# slice_v7_zp.net
KiCad netlist of a schematic drawn in EAGLE
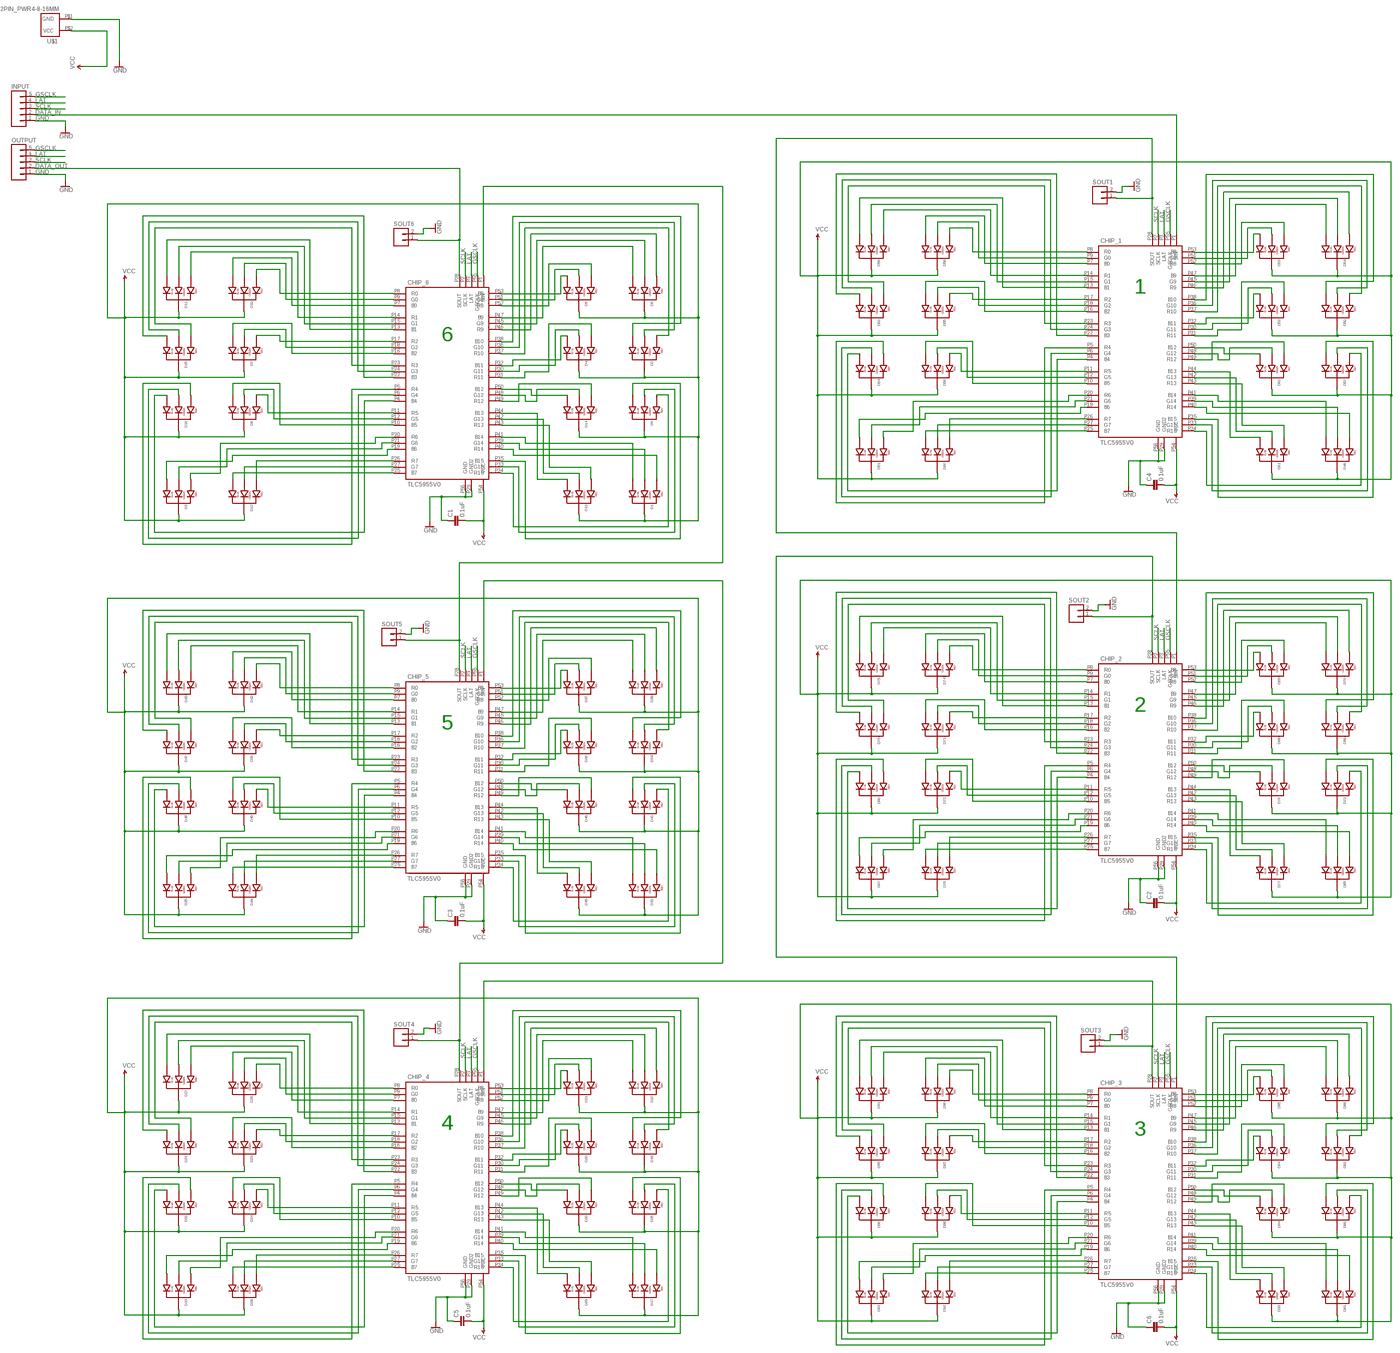
[diagram p0: schematic, sheet 1, overview]
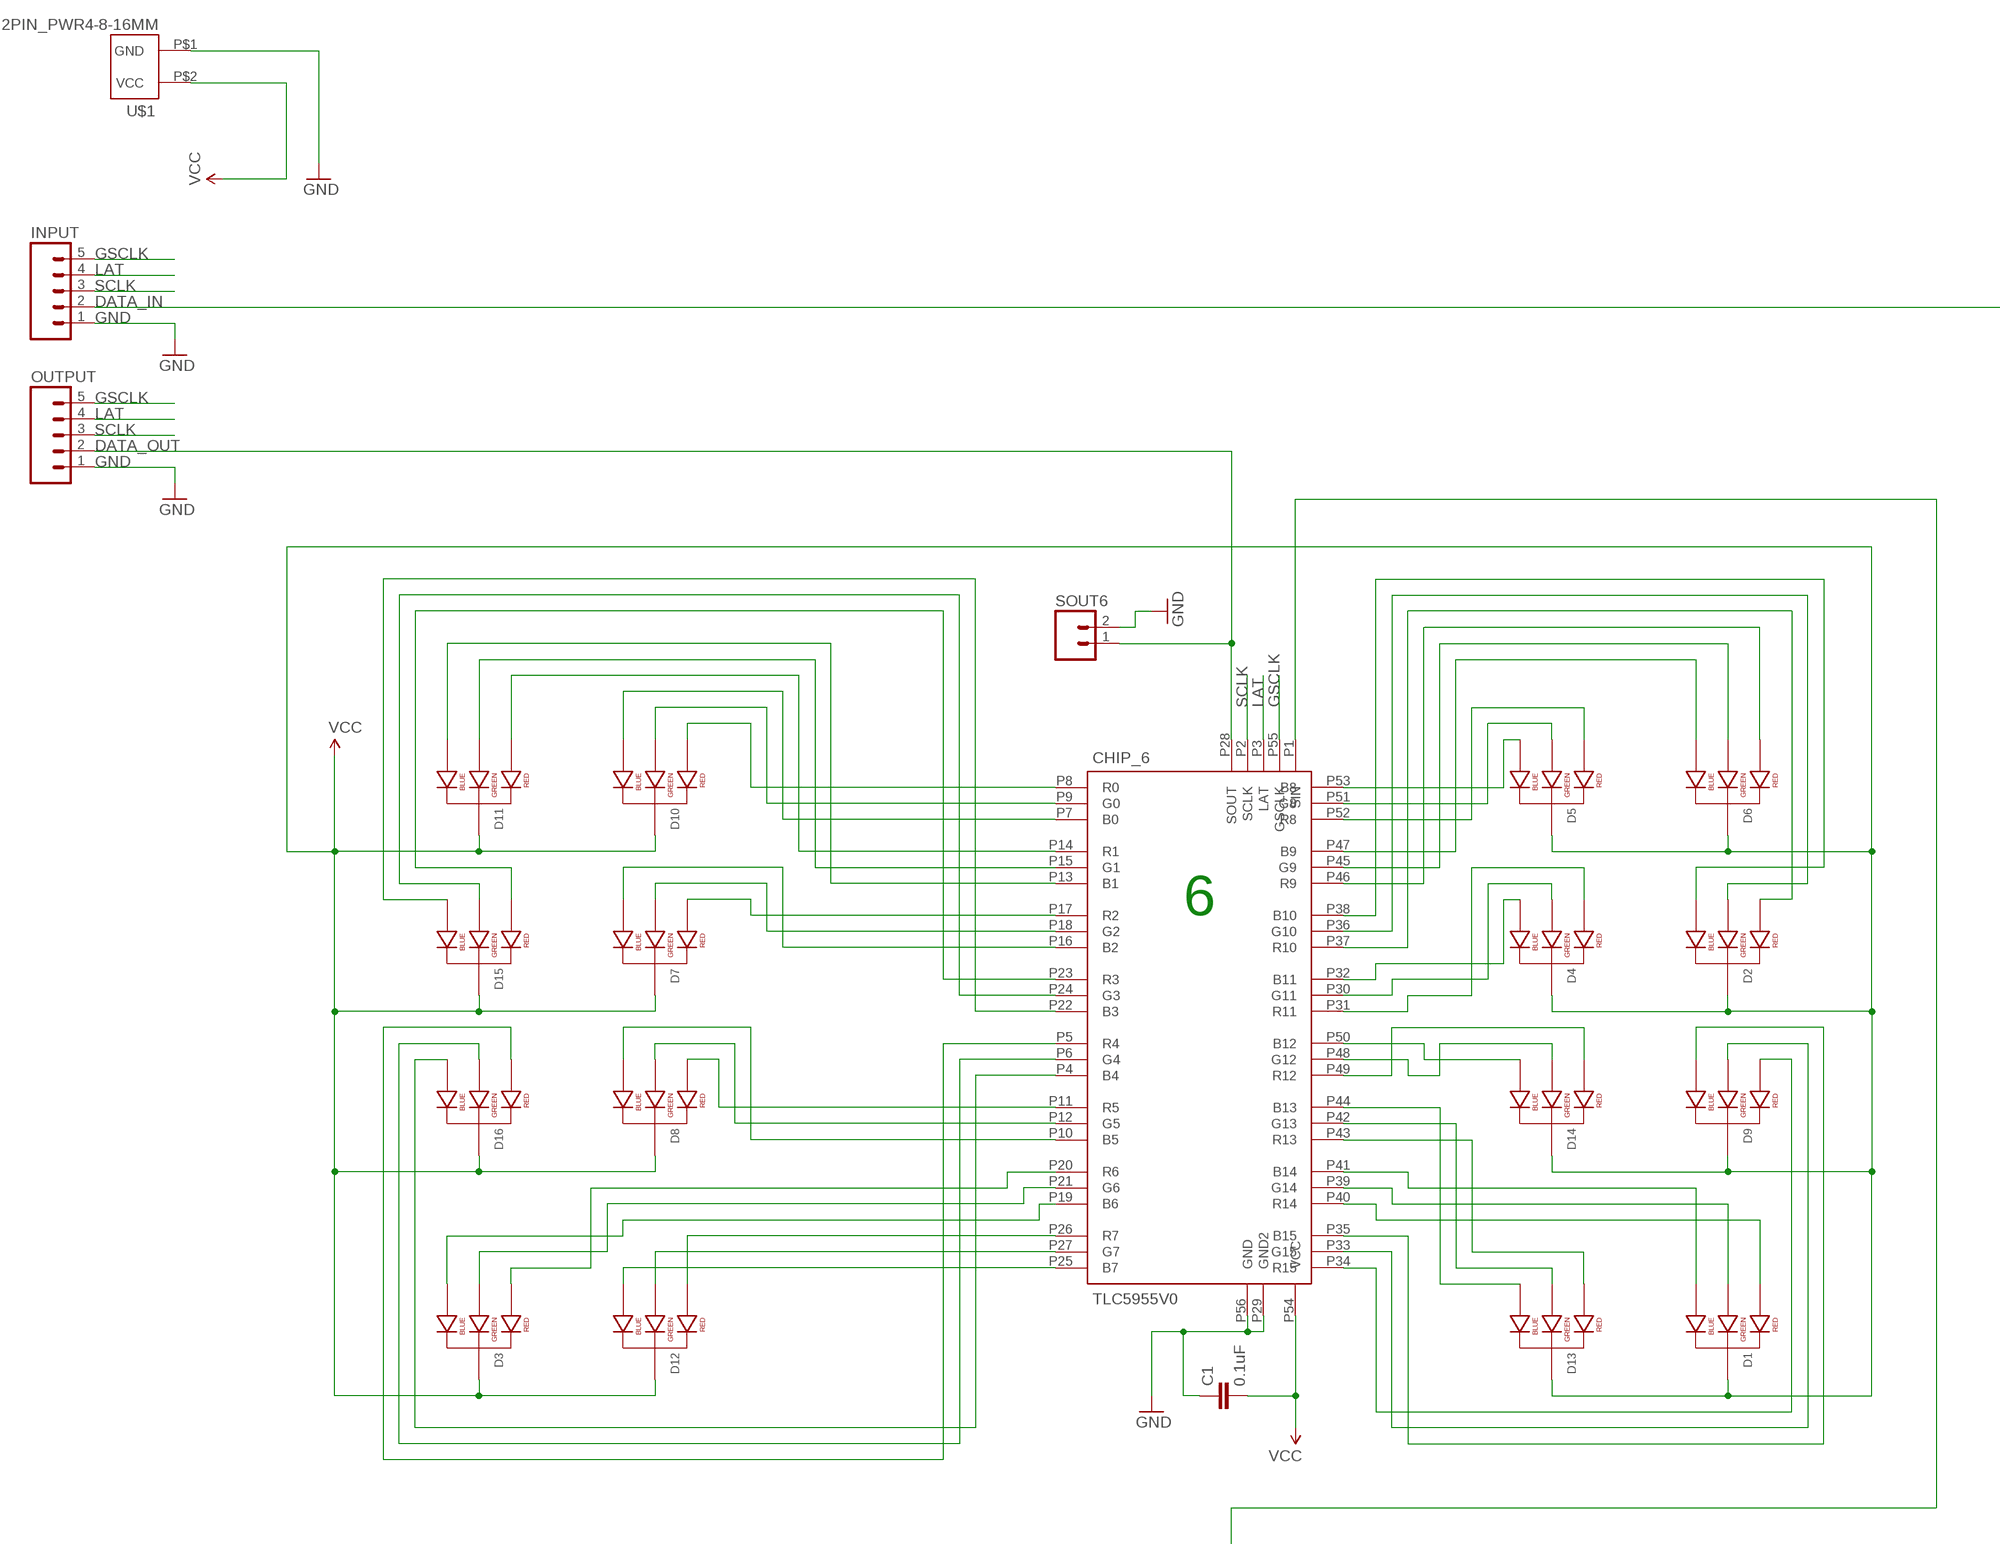
[diagram p1: schematic, sheet 1, part 1 of 4]
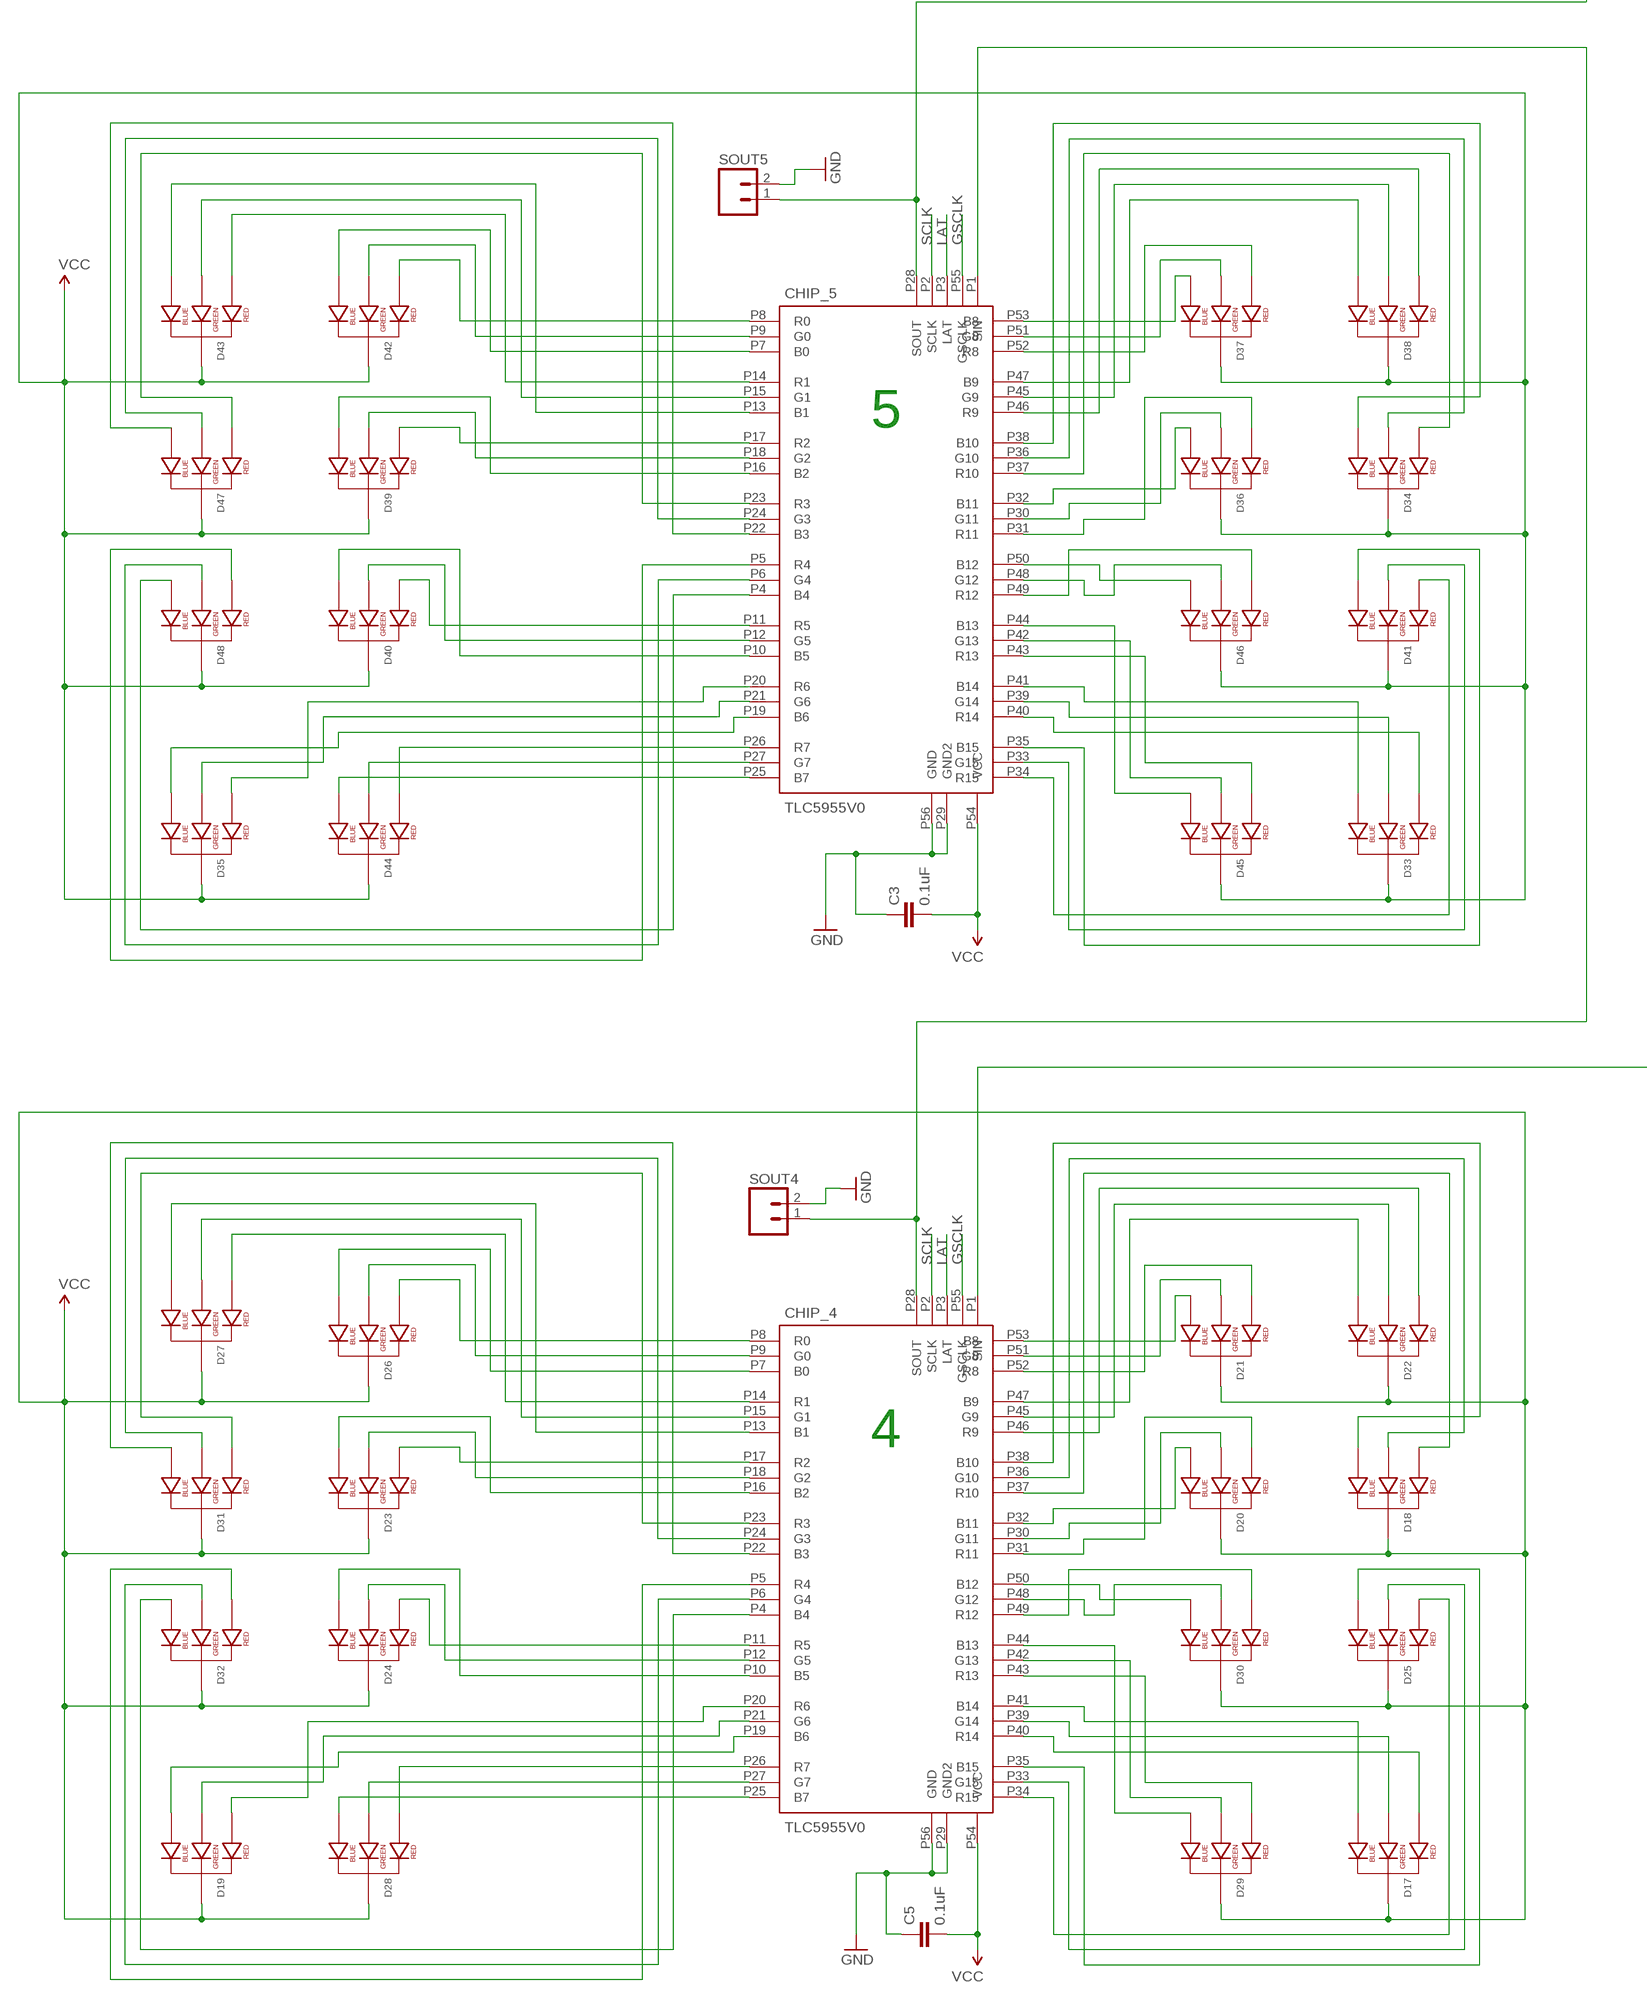
[diagram p2: schematic, sheet 1, part 2 of 4]
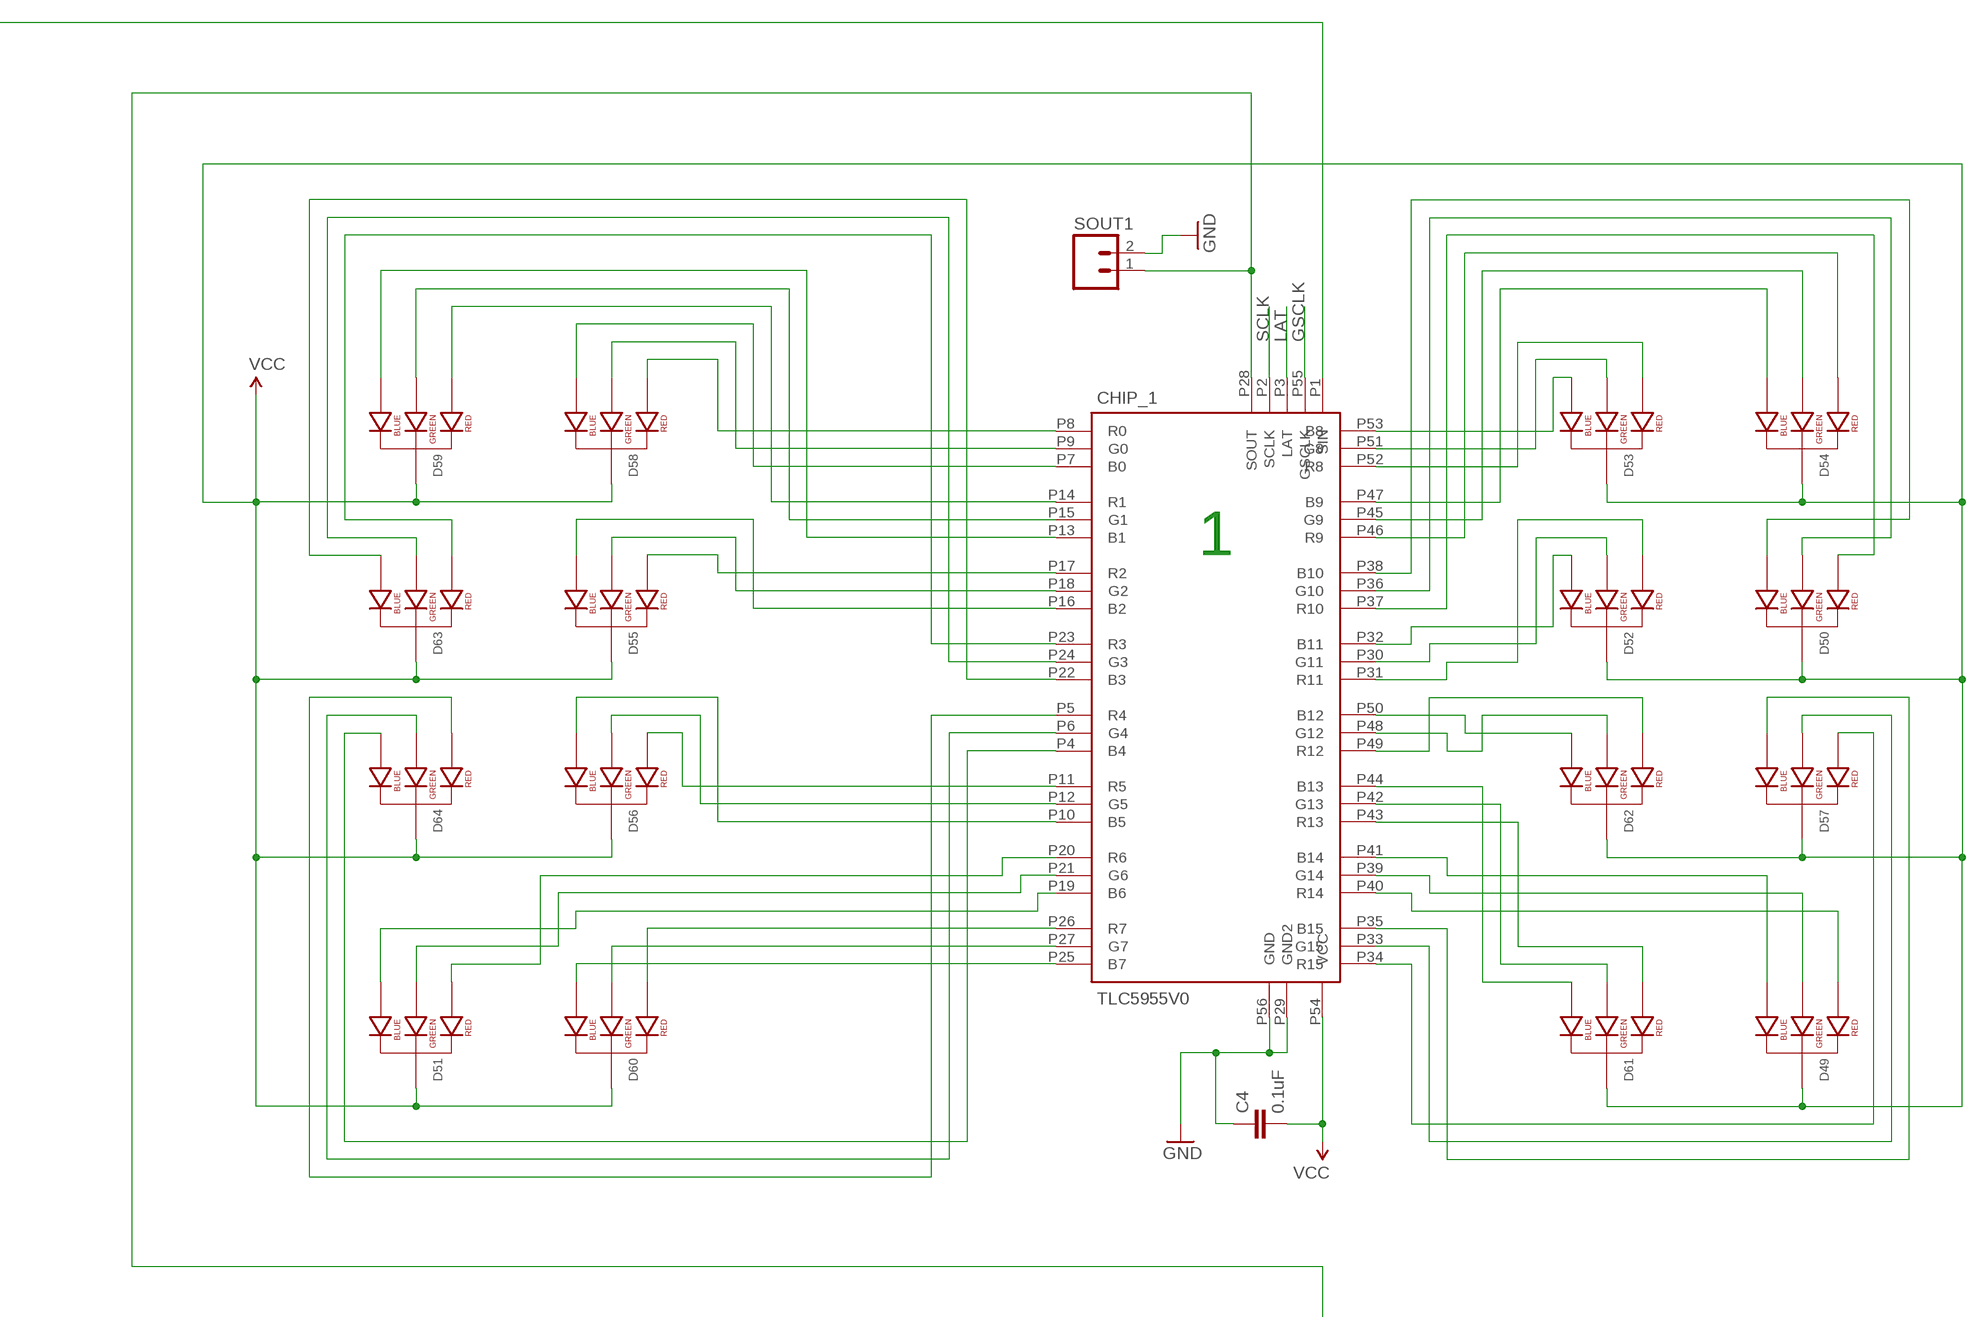
[diagram p3: schematic, sheet 1, part 3 of 4]
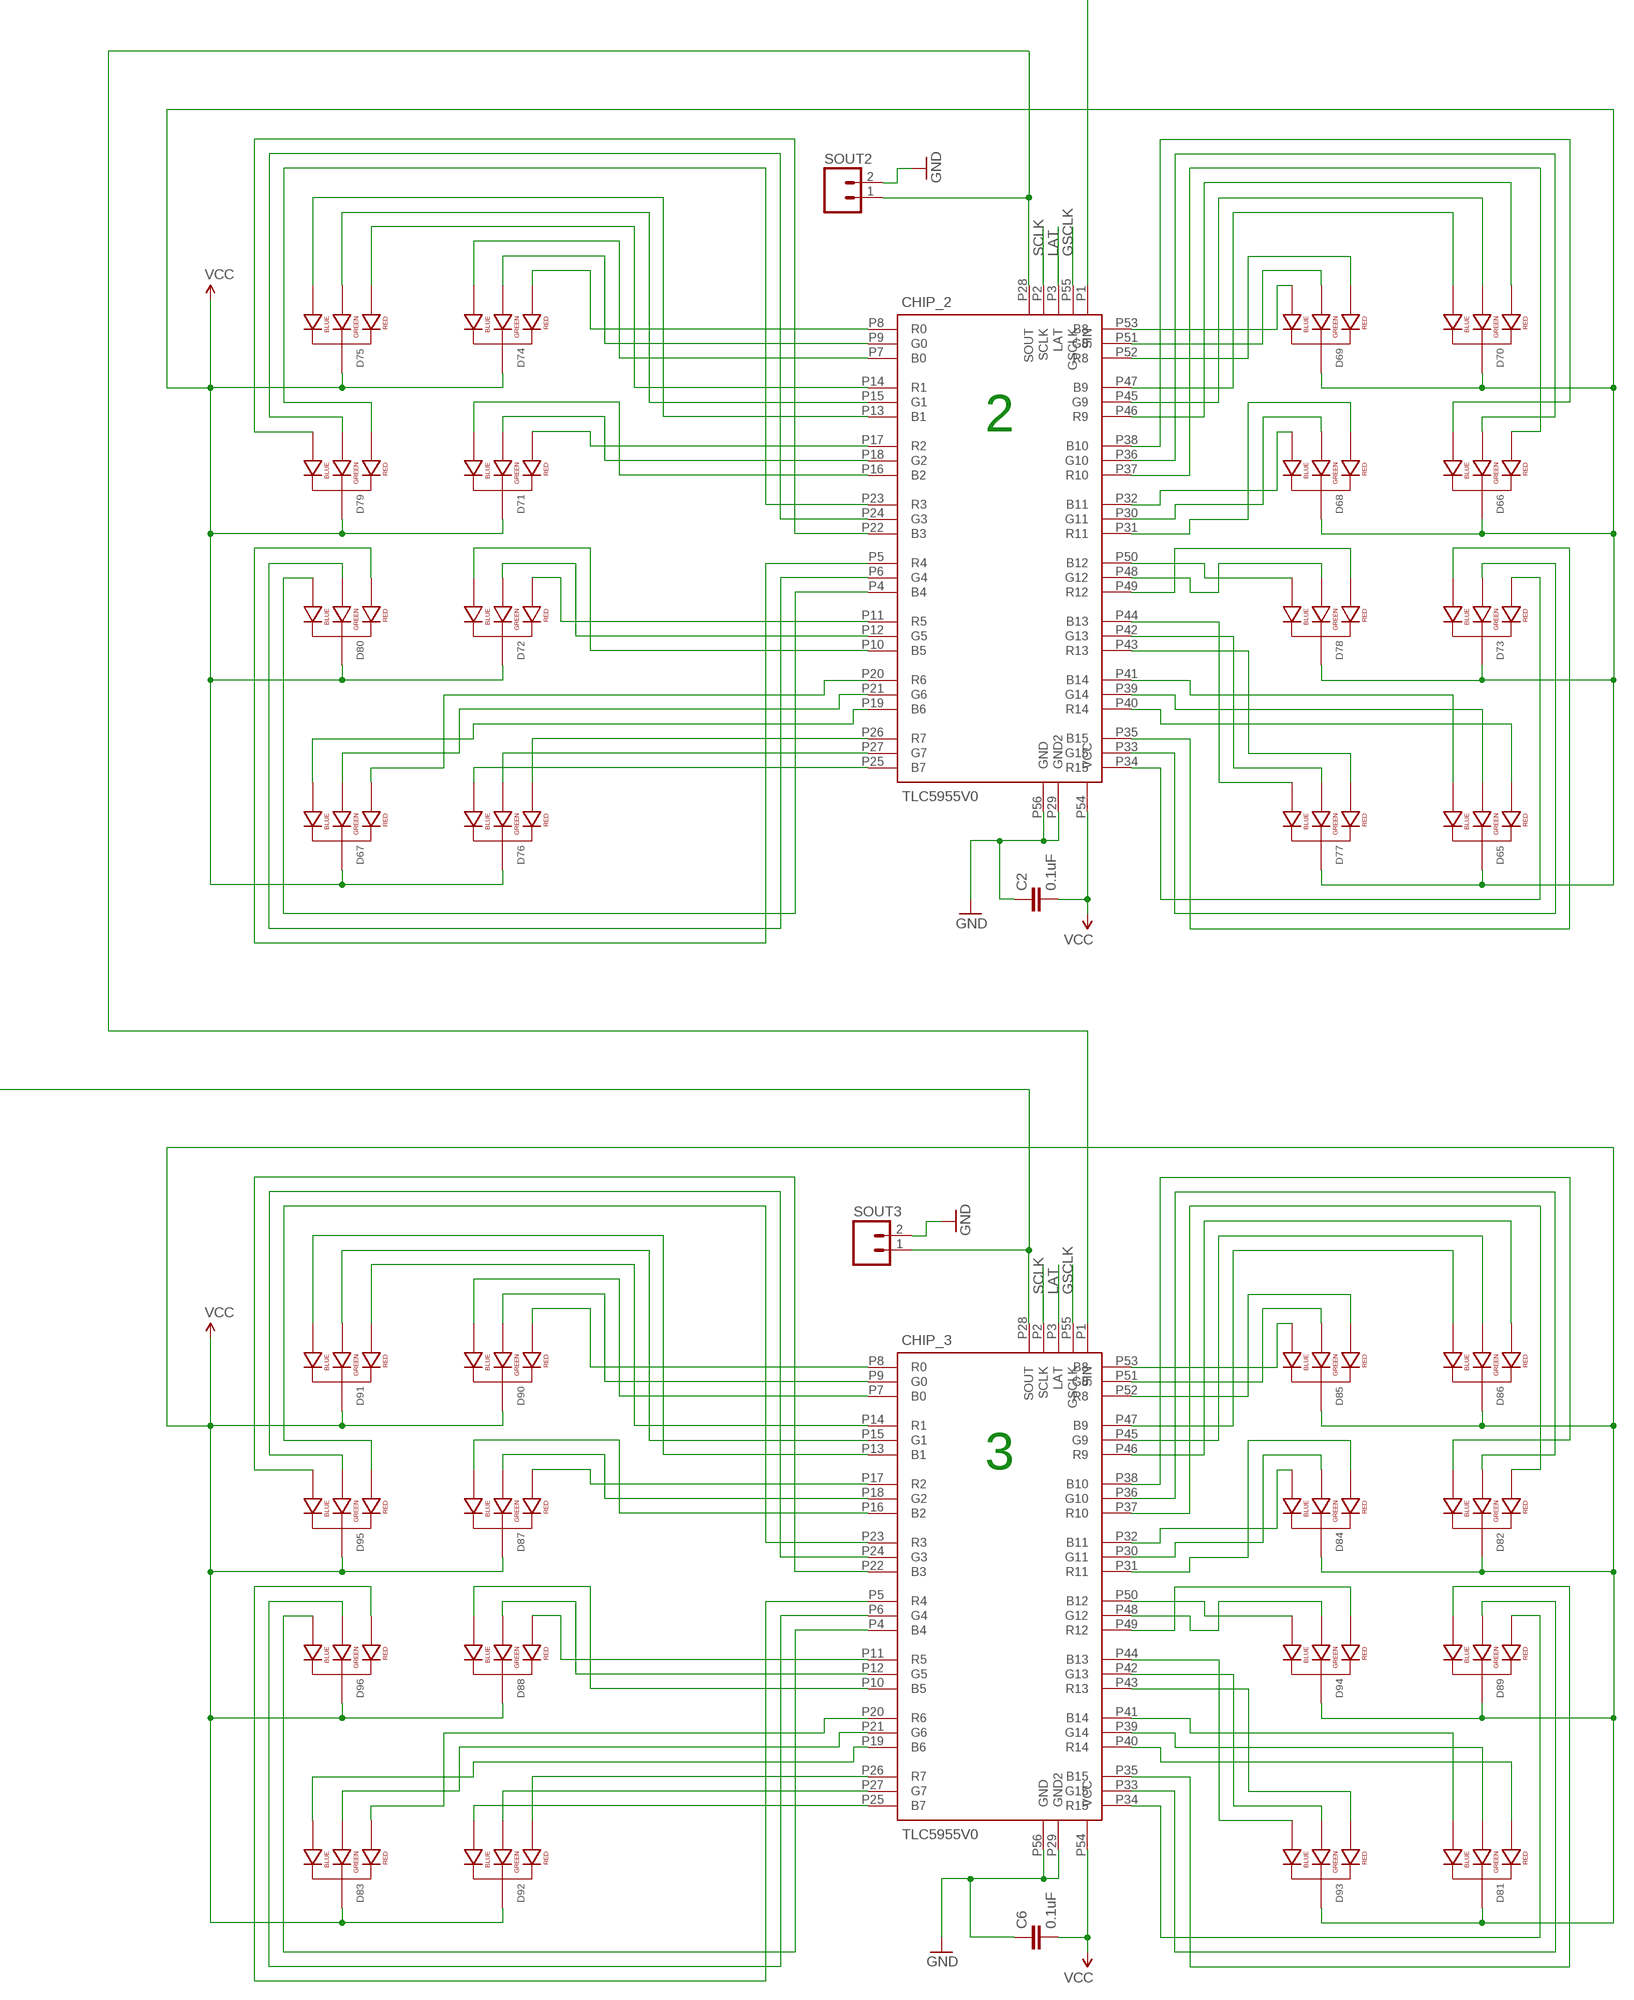
[diagram p4: schematic, sheet 1, part 4 of 4]

(export (version "E")
  (design (tool "Eeschema 10.0.6"))
  (components
    (comp (ref "C1")
      (value "0.1uF")
      (footprint "eagle-import:0603-CAP")
      (libsource (lib "eagle-import") (part "0.1UF-25V(+80/-20%)(0603)"))
    )
    (comp (ref "C2")
      (value "0.1uF")
      (footprint "eagle-import:0603-CAP")
      (libsource (lib "eagle-import") (part "0.1UF-25V(+80/-20%)(0603)"))
    )
    (comp (ref "C3")
      (value "0.1uF")
      (footprint "eagle-import:0603-CAP")
      (libsource (lib "eagle-import") (part "0.1UF-25V(+80/-20%)(0603)"))
    )
    (comp (ref "C4")
      (value "0.1uF")
      (footprint "eagle-import:0603-CAP")
      (libsource (lib "eagle-import") (part "0.1UF-25V(+80/-20%)(0603)"))
    )
    (comp (ref "C5")
      (value "0.1uF")
      (footprint "eagle-import:0603-CAP")
      (libsource (lib "eagle-import") (part "0.1UF-25V(+80/-20%)(0603)"))
    )
    (comp (ref "C6")
      (value "0.1uF")
      (footprint "eagle-import:0603-CAP")
      (libsource (lib "eagle-import") (part "0.1UF-25V(+80/-20%)(0603)"))
    )
    (comp (ref "CHIP_1")
      (value "TLC5955V0")
      (footprint "eagle-import:56-HTSSOP")
      (libsource (lib "eagle-import") (part "TLC5955V0"))
    )
    (comp (ref "CHIP_2")
      (value "TLC5955V0")
      (footprint "eagle-import:56-HTSSOP")
      (libsource (lib "eagle-import") (part "TLC5955V0"))
    )
    (comp (ref "CHIP_3")
      (value "TLC5955V0")
      (footprint "eagle-import:56-HTSSOP")
      (libsource (lib "eagle-import") (part "TLC5955V0"))
    )
    (comp (ref "CHIP_4")
      (value "TLC5955V0")
      (footprint "eagle-import:56-HTSSOP")
      (libsource (lib "eagle-import") (part "TLC5955V0"))
    )
    (comp (ref "CHIP_5")
      (value "TLC5955V0")
      (footprint "eagle-import:56-HTSSOP")
      (libsource (lib "eagle-import") (part "TLC5955V0"))
    )
    (comp (ref "CHIP_6")
      (value "TLC5955V0")
      (footprint "eagle-import:56-HTSSOP")
      (libsource (lib "eagle-import") (part "TLC5955V0"))
    )
    (comp (ref "D1")
      (value "LED-RGB-CC-THRUCLEAR")
      (footprint "eagle-import:LED-RGB-THRU")
      (libsource (lib "eagle-import") (part "LED-RGB-CC-THRUCLEAR"))
    )
    (comp (ref "D2")
      (value "LED-RGB-CC-THRUCLEAR")
      (footprint "eagle-import:LED-RGB-THRU")
      (libsource (lib "eagle-import") (part "LED-RGB-CC-THRUCLEAR"))
    )
    (comp (ref "D3")
      (value "LED-RGB-CC-THRUCLEAR")
      (footprint "eagle-import:LED-RGB-THRU")
      (libsource (lib "eagle-import") (part "LED-RGB-CC-THRUCLEAR"))
    )
    (comp (ref "D4")
      (value "LED-RGB-CC-THRUCLEAR")
      (footprint "eagle-import:LED-RGB-THRU")
      (libsource (lib "eagle-import") (part "LED-RGB-CC-THRUCLEAR"))
    )
    (comp (ref "D5")
      (value "LED-RGB-CC-THRUCLEAR")
      (footprint "eagle-import:LED-RGB-THRU")
      (libsource (lib "eagle-import") (part "LED-RGB-CC-THRUCLEAR"))
    )
    (comp (ref "D6")
      (value "LED-RGB-CC-THRUCLEAR")
      (footprint "eagle-import:LED-RGB-THRU")
      (libsource (lib "eagle-import") (part "LED-RGB-CC-THRUCLEAR"))
    )
    (comp (ref "D7")
      (value "LED-RGB-CC-THRUCLEAR")
      (footprint "eagle-import:LED-RGB-THRU")
      (libsource (lib "eagle-import") (part "LED-RGB-CC-THRUCLEAR"))
    )
    (comp (ref "D8")
      (value "LED-RGB-CC-THRUCLEAR")
      (footprint "eagle-import:LED-RGB-THRU")
      (libsource (lib "eagle-import") (part "LED-RGB-CC-THRUCLEAR"))
    )
    (comp (ref "D9")
      (value "LED-RGB-CC-THRUCLEAR")
      (footprint "eagle-import:LED-RGB-THRU")
      (libsource (lib "eagle-import") (part "LED-RGB-CC-THRUCLEAR"))
    )
    (comp (ref "D10")
      (value "LED-RGB-CC-THRUCLEAR")
      (footprint "eagle-import:LED-RGB-THRU")
      (libsource (lib "eagle-import") (part "LED-RGB-CC-THRUCLEAR"))
    )
    (comp (ref "D11")
      (value "LED-RGB-CC-THRUDIFFUSE")
      (footprint "eagle-import:LED-RGB-THRU")
      (libsource (lib "eagle-import") (part "LED-RGB-CC-THRUCLEAR"))
    )
    (comp (ref "D12")
      (value "LED-RGB-CC-THRUCLEAR")
      (footprint "eagle-import:LED-RGB-THRU")
      (libsource (lib "eagle-import") (part "LED-RGB-CC-THRUCLEAR"))
    )
    (comp (ref "D13")
      (value "LED-RGB-CC-THRUCLEAR")
      (footprint "eagle-import:LED-RGB-THRU")
      (libsource (lib "eagle-import") (part "LED-RGB-CC-THRUCLEAR"))
    )
    (comp (ref "D14")
      (value "LED-RGB-CC-THRUCLEAR")
      (footprint "eagle-import:LED-RGB-THRU")
      (libsource (lib "eagle-import") (part "LED-RGB-CC-THRUCLEAR"))
    )
    (comp (ref "D15")
      (value "LED-RGB-CC-THRUCLEAR")
      (footprint "eagle-import:LED-RGB-THRU")
      (libsource (lib "eagle-import") (part "LED-RGB-CC-THRUCLEAR"))
    )
    (comp (ref "D16")
      (value "LED-RGB-CC-THRUCLEAR")
      (footprint "eagle-import:LED-RGB-THRU")
      (libsource (lib "eagle-import") (part "LED-RGB-CC-THRUCLEAR"))
    )
    (comp (ref "D17")
      (value "LED-RGB-CC-THRUCLEAR")
      (footprint "eagle-import:LED-RGB-THRU")
      (libsource (lib "eagle-import") (part "LED-RGB-CC-THRUCLEAR"))
    )
    (comp (ref "D18")
      (value "LED-RGB-CC-THRUCLEAR")
      (footprint "eagle-import:LED-RGB-THRU")
      (libsource (lib "eagle-import") (part "LED-RGB-CC-THRUCLEAR"))
    )
    (comp (ref "D19")
      (value "LED-RGB-CC-THRUCLEAR")
      (footprint "eagle-import:LED-RGB-THRU")
      (libsource (lib "eagle-import") (part "LED-RGB-CC-THRUCLEAR"))
    )
    (comp (ref "D20")
      (value "LED-RGB-CC-THRUCLEAR")
      (footprint "eagle-import:LED-RGB-THRU")
      (libsource (lib "eagle-import") (part "LED-RGB-CC-THRUCLEAR"))
    )
    (comp (ref "D21")
      (value "LED-RGB-CC-THRUCLEAR")
      (footprint "eagle-import:LED-RGB-THRU")
      (libsource (lib "eagle-import") (part "LED-RGB-CC-THRUCLEAR"))
    )
    (comp (ref "D22")
      (value "LED-RGB-CC-THRUCLEAR")
      (footprint "eagle-import:LED-RGB-THRU")
      (libsource (lib "eagle-import") (part "LED-RGB-CC-THRUCLEAR"))
    )
    (comp (ref "D23")
      (value "LED-RGB-CC-THRUCLEAR")
      (footprint "eagle-import:LED-RGB-THRU")
      (libsource (lib "eagle-import") (part "LED-RGB-CC-THRUCLEAR"))
    )
    (comp (ref "D24")
      (value "LED-RGB-CC-THRUCLEAR")
      (footprint "eagle-import:LED-RGB-THRU")
      (libsource (lib "eagle-import") (part "LED-RGB-CC-THRUCLEAR"))
    )
    (comp (ref "D25")
      (value "LED-RGB-CC-THRUCLEAR")
      (footprint "eagle-import:LED-RGB-THRU")
      (libsource (lib "eagle-import") (part "LED-RGB-CC-THRUCLEAR"))
    )
    (comp (ref "D26")
      (value "LED-RGB-CC-THRUCLEAR")
      (footprint "eagle-import:LED-RGB-THRU")
      (libsource (lib "eagle-import") (part "LED-RGB-CC-THRUCLEAR"))
    )
    (comp (ref "D27")
      (value "LED-RGB-CC-THRUCLEAR")
      (footprint "eagle-import:LED-RGB-THRU")
      (libsource (lib "eagle-import") (part "LED-RGB-CC-THRUCLEAR"))
    )
    (comp (ref "D28")
      (value "LED-RGB-CC-THRUCLEAR")
      (footprint "eagle-import:LED-RGB-THRU")
      (libsource (lib "eagle-import") (part "LED-RGB-CC-THRUCLEAR"))
    )
    (comp (ref "D29")
      (value "LED-RGB-CC-THRUCLEAR")
      (footprint "eagle-import:LED-RGB-THRU")
      (libsource (lib "eagle-import") (part "LED-RGB-CC-THRUCLEAR"))
    )
    (comp (ref "D30")
      (value "LED-RGB-CC-THRUCLEAR")
      (footprint "eagle-import:LED-RGB-THRU")
      (libsource (lib "eagle-import") (part "LED-RGB-CC-THRUCLEAR"))
    )
    (comp (ref "D31")
      (value "LED-RGB-CC-THRUCLEAR")
      (footprint "eagle-import:LED-RGB-THRU")
      (libsource (lib "eagle-import") (part "LED-RGB-CC-THRUCLEAR"))
    )
    (comp (ref "D32")
      (value "LED-RGB-CC-THRUCLEAR")
      (footprint "eagle-import:LED-RGB-THRU")
      (libsource (lib "eagle-import") (part "LED-RGB-CC-THRUCLEAR"))
    )
    (comp (ref "D33")
      (value "LED-RGB-CC-THRUCLEAR")
      (footprint "eagle-import:LED-RGB-THRU")
      (libsource (lib "eagle-import") (part "LED-RGB-CC-THRUCLEAR"))
    )
    (comp (ref "D34")
      (value "LED-RGB-CC-THRUCLEAR")
      (footprint "eagle-import:LED-RGB-THRU")
      (libsource (lib "eagle-import") (part "LED-RGB-CC-THRUCLEAR"))
    )
    (comp (ref "D35")
      (value "1")
      (footprint "eagle-import:LED-RGB-THRU")
      (libsource (lib "eagle-import") (part "LED-RGB-CC-THRUCLEAR"))
    )
    (comp (ref "D36")
      (value "LED-RGB-CC-THRUCLEAR")
      (footprint "eagle-import:LED-RGB-THRU")
      (libsource (lib "eagle-import") (part "LED-RGB-CC-THRUCLEAR"))
    )
    (comp (ref "D37")
      (value "LED-RGB-CC-THRUCLEAR")
      (footprint "eagle-import:LED-RGB-THRU")
      (libsource (lib "eagle-import") (part "LED-RGB-CC-THRUCLEAR"))
    )
    (comp (ref "D38")
      (value "LED-RGB-CC-THRUCLEAR")
      (footprint "eagle-import:LED-RGB-THRU")
      (libsource (lib "eagle-import") (part "LED-RGB-CC-THRUCLEAR"))
    )
    (comp (ref "D39")
      (value "LED-RGB-CC-THRUCLEAR")
      (footprint "eagle-import:LED-RGB-THRU")
      (libsource (lib "eagle-import") (part "LED-RGB-CC-THRUCLEAR"))
    )
    (comp (ref "D40")
      (value "LED-RGB-CC-THRUCLEAR")
      (footprint "eagle-import:LED-RGB-THRU")
      (libsource (lib "eagle-import") (part "LED-RGB-CC-THRUCLEAR"))
    )
    (comp (ref "D41")
      (value "LED-RGB-CC-THRUCLEAR")
      (footprint "eagle-import:LED-RGB-THRU")
      (libsource (lib "eagle-import") (part "LED-RGB-CC-THRUCLEAR"))
    )
    (comp (ref "D42")
      (value "LED-RGB-CC-THRUCLEAR")
      (footprint "eagle-import:LED-RGB-THRU")
      (libsource (lib "eagle-import") (part "LED-RGB-CC-THRUCLEAR"))
    )
    (comp (ref "D43")
      (value "LED-RGB-CC-THRUCLEAR")
      (footprint "eagle-import:LED-RGB-THRU")
      (libsource (lib "eagle-import") (part "LED-RGB-CC-THRUCLEAR"))
    )
    (comp (ref "D44")
      (value "LED-RGB-CC-THRUCLEAR")
      (footprint "eagle-import:LED-RGB-THRU")
      (libsource (lib "eagle-import") (part "LED-RGB-CC-THRUCLEAR"))
    )
    (comp (ref "D45")
      (value "LED-RGB-CC-THRUCLEAR")
      (footprint "eagle-import:LED-RGB-THRU")
      (libsource (lib "eagle-import") (part "LED-RGB-CC-THRUCLEAR"))
    )
    (comp (ref "D46")
      (value "LED-RGB-CC-THRUCLEAR")
      (footprint "eagle-import:LED-RGB-THRU")
      (libsource (lib "eagle-import") (part "LED-RGB-CC-THRUCLEAR"))
    )
    (comp (ref "D47")
      (value "LED-RGB-CC-THRUCLEAR")
      (footprint "eagle-import:LED-RGB-THRU")
      (libsource (lib "eagle-import") (part "LED-RGB-CC-THRUCLEAR"))
    )
    (comp (ref "D48")
      (value "LED-RGB-CC-THRUCLEAR")
      (footprint "eagle-import:LED-RGB-THRU")
      (libsource (lib "eagle-import") (part "LED-RGB-CC-THRUCLEAR"))
    )
    (comp (ref "D49")
      (value "LED-RGB-CC-THRUCLEAR")
      (footprint "eagle-import:LED-RGB-THRU")
      (libsource (lib "eagle-import") (part "LED-RGB-CC-THRUCLEAR"))
    )
    (comp (ref "D50")
      (value "LED-RGB-CC-THRUCLEAR")
      (footprint "eagle-import:LED-RGB-THRU")
      (libsource (lib "eagle-import") (part "LED-RGB-CC-THRUCLEAR"))
    )
    (comp (ref "D51")
      (value "LED-RGB-CC-THRUCLEAR")
      (footprint "eagle-import:LED-RGB-THRU")
      (libsource (lib "eagle-import") (part "LED-RGB-CC-THRUCLEAR"))
    )
    (comp (ref "D52")
      (value "LED-RGB-CC-THRUCLEAR")
      (footprint "eagle-import:LED-RGB-THRU")
      (libsource (lib "eagle-import") (part "LED-RGB-CC-THRUCLEAR"))
    )
    (comp (ref "D53")
      (value "LED-RGB-CC-THRUCLEAR")
      (footprint "eagle-import:LED-RGB-THRU")
      (libsource (lib "eagle-import") (part "LED-RGB-CC-THRUCLEAR"))
    )
    (comp (ref "D54")
      (value "LED-RGB-CC-THRUCLEAR")
      (footprint "eagle-import:LED-RGB-THRU")
      (libsource (lib "eagle-import") (part "LED-RGB-CC-THRUCLEAR"))
    )
    (comp (ref "D55")
      (value "LED-RGB-CC-THRUCLEAR")
      (footprint "eagle-import:LED-RGB-THRU")
      (libsource (lib "eagle-import") (part "LED-RGB-CC-THRUCLEAR"))
    )
    (comp (ref "D56")
      (value "LED-RGB-CC-THRUCLEAR")
      (footprint "eagle-import:LED-RGB-THRU")
      (libsource (lib "eagle-import") (part "LED-RGB-CC-THRUCLEAR"))
    )
    (comp (ref "D57")
      (value "LED-RGB-CC-THRUCLEAR")
      (footprint "eagle-import:LED-RGB-THRU")
      (libsource (lib "eagle-import") (part "LED-RGB-CC-THRUCLEAR"))
    )
    (comp (ref "D58")
      (value "LED-RGB-CC-THRUCLEAR")
      (footprint "eagle-import:LED-RGB-THRU")
      (libsource (lib "eagle-import") (part "LED-RGB-CC-THRUCLEAR"))
    )
    (comp (ref "D59")
      (value "LED-RGB-CC-THRUCLEAR")
      (footprint "eagle-import:LED-RGB-THRU")
      (libsource (lib "eagle-import") (part "LED-RGB-CC-THRUCLEAR"))
    )
    (comp (ref "D60")
      (value "LED-RGB-CC-THRUCLEAR")
      (footprint "eagle-import:LED-RGB-THRU")
      (libsource (lib "eagle-import") (part "LED-RGB-CC-THRUCLEAR"))
    )
    (comp (ref "D61")
      (value "LED-RGB-CC-THRUCLEAR")
      (footprint "eagle-import:LED-RGB-THRU")
      (libsource (lib "eagle-import") (part "LED-RGB-CC-THRUCLEAR"))
    )
    (comp (ref "D62")
      (value "LED-RGB-CC-THRUCLEAR")
      (footprint "eagle-import:LED-RGB-THRU")
      (libsource (lib "eagle-import") (part "LED-RGB-CC-THRUCLEAR"))
    )
    (comp (ref "D63")
      (value "LED-RGB-CC-THRUCLEAR")
      (footprint "eagle-import:LED-RGB-THRU")
      (libsource (lib "eagle-import") (part "LED-RGB-CC-THRUCLEAR"))
    )
    (comp (ref "D64")
      (value "LED-RGB-CC-THRUCLEAR")
      (footprint "eagle-import:LED-RGB-THRU")
      (libsource (lib "eagle-import") (part "LED-RGB-CC-THRUCLEAR"))
    )
    (comp (ref "D65")
      (value "LED-RGB-CC-THRUCLEAR")
      (footprint "eagle-import:LED-RGB-THRU")
      (libsource (lib "eagle-import") (part "LED-RGB-CC-THRUCLEAR"))
    )
    (comp (ref "D66")
      (value "LED-RGB-CC-THRUCLEAR")
      (footprint "eagle-import:LED-RGB-THRU")
      (libsource (lib "eagle-import") (part "LED-RGB-CC-THRUCLEAR"))
    )
    (comp (ref "D67")
      (value "LED-RGB-CC-THRUCLEAR")
      (footprint "eagle-import:LED-RGB-THRU")
      (libsource (lib "eagle-import") (part "LED-RGB-CC-THRUCLEAR"))
    )
    (comp (ref "D68")
      (value "LED-RGB-CC-THRUCLEAR")
      (footprint "eagle-import:LED-RGB-THRU")
      (libsource (lib "eagle-import") (part "LED-RGB-CC-THRUCLEAR"))
    )
    (comp (ref "D69")
      (value "LED-RGB-CC-THRUCLEAR")
      (footprint "eagle-import:LED-RGB-THRU")
      (libsource (lib "eagle-import") (part "LED-RGB-CC-THRUCLEAR"))
    )
    (comp (ref "D70")
      (value "LED-RGB-CC-THRUCLEAR")
      (footprint "eagle-import:LED-RGB-THRU")
      (libsource (lib "eagle-import") (part "LED-RGB-CC-THRUCLEAR"))
    )
    (comp (ref "D71")
      (value "LED-RGB-CC-THRUCLEAR")
      (footprint "eagle-import:LED-RGB-THRU")
      (libsource (lib "eagle-import") (part "LED-RGB-CC-THRUCLEAR"))
    )
    (comp (ref "D72")
      (value "LED-RGB-CC-THRUCLEAR")
      (footprint "eagle-import:LED-RGB-THRU")
      (libsource (lib "eagle-import") (part "LED-RGB-CC-THRUCLEAR"))
    )
    (comp (ref "D73")
      (value "LED-RGB-CC-THRUCLEAR")
      (footprint "eagle-import:LED-RGB-THRU")
      (libsource (lib "eagle-import") (part "LED-RGB-CC-THRUCLEAR"))
    )
    (comp (ref "D74")
      (value "LED-RGB-CC-THRUCLEAR")
      (footprint "eagle-import:LED-RGB-THRU")
      (libsource (lib "eagle-import") (part "LED-RGB-CC-THRUCLEAR"))
    )
    (comp (ref "D75")
      (value "LED-RGB-CC-THRUCLEAR")
      (footprint "eagle-import:LED-RGB-THRU")
      (libsource (lib "eagle-import") (part "LED-RGB-CC-THRUCLEAR"))
    )
    (comp (ref "D76")
      (value "LED-RGB-CC-THRUCLEAR")
      (footprint "eagle-import:LED-RGB-THRU")
      (libsource (lib "eagle-import") (part "LED-RGB-CC-THRUCLEAR"))
    )
    (comp (ref "D77")
      (value "LED-RGB-CC-THRUCLEAR")
      (footprint "eagle-import:LED-RGB-THRU")
      (libsource (lib "eagle-import") (part "LED-RGB-CC-THRUCLEAR"))
    )
    (comp (ref "D78")
      (value "LED-RGB-CC-THRUCLEAR")
      (footprint "eagle-import:LED-RGB-THRU")
      (libsource (lib "eagle-import") (part "LED-RGB-CC-THRUCLEAR"))
    )
    (comp (ref "D79")
      (value "LED-RGB-CC-THRUCLEAR")
      (footprint "eagle-import:LED-RGB-THRU")
      (libsource (lib "eagle-import") (part "LED-RGB-CC-THRUCLEAR"))
    )
    (comp (ref "D80")
      (value "LED-RGB-CC-THRUCLEAR")
      (footprint "eagle-import:LED-RGB-THRU")
      (libsource (lib "eagle-import") (part "LED-RGB-CC-THRUCLEAR"))
    )
    (comp (ref "D81")
      (value "LED-RGB-CC-THRUCLEAR")
      (footprint "eagle-import:LED-RGB-THRU")
      (libsource (lib "eagle-import") (part "LED-RGB-CC-THRUCLEAR"))
    )
    (comp (ref "D82")
      (value "LED-RGB-CC-THRUCLEAR")
      (footprint "eagle-import:LED-RGB-THRU")
      (libsource (lib "eagle-import") (part "LED-RGB-CC-THRUCLEAR"))
    )
    (comp (ref "D83")
      (value "LED-RGB-CC-THRUCLEAR")
      (footprint "eagle-import:LED-RGB-THRU")
      (libsource (lib "eagle-import") (part "LED-RGB-CC-THRUCLEAR"))
    )
    (comp (ref "D84")
      (value "LED-RGB-CC-THRUCLEAR")
      (footprint "eagle-import:LED-RGB-THRU")
      (libsource (lib "eagle-import") (part "LED-RGB-CC-THRUCLEAR"))
    )
    (comp (ref "D85")
      (value "LED-RGB-CC-THRUCLEAR")
      (footprint "eagle-import:LED-RGB-THRU")
      (libsource (lib "eagle-import") (part "LED-RGB-CC-THRUCLEAR"))
    )
    (comp (ref "D86")
      (value "LED-RGB-CC-THRUCLEAR")
      (footprint "eagle-import:LED-RGB-THRU")
      (libsource (lib "eagle-import") (part "LED-RGB-CC-THRUCLEAR"))
    )
    (comp (ref "D87")
      (value "LED-RGB-CC-THRUCLEAR")
      (footprint "eagle-import:LED-RGB-THRU")
      (libsource (lib "eagle-import") (part "LED-RGB-CC-THRUCLEAR"))
    )
    (comp (ref "D88")
      (value "LED-RGB-CC-THRUCLEAR")
      (footprint "eagle-import:LED-RGB-THRU")
      (libsource (lib "eagle-import") (part "LED-RGB-CC-THRUCLEAR"))
    )
    (comp (ref "D89")
      (value "LED-RGB-CC-THRUCLEAR")
      (footprint "eagle-import:LED-RGB-THRU")
      (libsource (lib "eagle-import") (part "LED-RGB-CC-THRUCLEAR"))
    )
    (comp (ref "D90")
      (value "LED-RGB-CC-THRUCLEAR")
      (footprint "eagle-import:LED-RGB-THRU")
      (libsource (lib "eagle-import") (part "LED-RGB-CC-THRUCLEAR"))
    )
    (comp (ref "D91")
      (value "LED-RGB-CC-THRUCLEAR")
      (footprint "eagle-import:LED-RGB-THRU")
      (libsource (lib "eagle-import") (part "LED-RGB-CC-THRUCLEAR"))
    )
    (comp (ref "D92")
      (value "LED-RGB-CC-THRUCLEAR")
      (footprint "eagle-import:LED-RGB-THRU")
      (libsource (lib "eagle-import") (part "LED-RGB-CC-THRUCLEAR"))
    )
    (comp (ref "D93")
      (value "LED-RGB-CC-THRUCLEAR")
      (footprint "eagle-import:LED-RGB-THRU")
      (libsource (lib "eagle-import") (part "LED-RGB-CC-THRUCLEAR"))
    )
    (comp (ref "D94")
      (value "LED-RGB-CC-THRUCLEAR")
      (footprint "eagle-import:LED-RGB-THRU")
      (libsource (lib "eagle-import") (part "LED-RGB-CC-THRUCLEAR"))
    )
    (comp (ref "D95")
      (value "LED-RGB-CC-THRUCLEAR")
      (footprint "eagle-import:LED-RGB-THRU")
      (libsource (lib "eagle-import") (part "LED-RGB-CC-THRUCLEAR"))
    )
    (comp (ref "D96")
      (value "LED-RGB-CC-THRUCLEAR")
      (footprint "eagle-import:LED-RGB-THRU")
      (libsource (lib "eagle-import") (part "LED-RGB-CC-THRUCLEAR"))
    )
    (comp (ref "INPUT")
      (value "M05LOCK_LONGPADS")
      (footprint "eagle-import:1X05_LOCK_LONGPADS")
      (libsource (lib "eagle-import") (part "M05LOCK_LONGPADS"))
    )
    (comp (ref "OUTPUT")
      (value "M05LOCK_LONGPADS")
      (footprint "eagle-import:1X05_LOCK_LONGPADS")
      (libsource (lib "eagle-import") (part "M05LOCK_LONGPADS"))
    )
    (comp (ref "SOUT1")
      (value "M02LOCK")
      (footprint "eagle-import:1X02_LOCK")
      (libsource (lib "eagle-import") (part "M02LOCK"))
    )
    (comp (ref "SOUT2")
      (value "M02LOCK")
      (footprint "eagle-import:1X02_LOCK")
      (libsource (lib "eagle-import") (part "M02LOCK"))
    )
    (comp (ref "SOUT3")
      (value "M02LOCK")
      (footprint "eagle-import:1X02_LOCK")
      (libsource (lib "eagle-import") (part "M02LOCK"))
    )
    (comp (ref "SOUT4")
      (value "M02LOCK")
      (footprint "eagle-import:1X02_LOCK")
      (libsource (lib "eagle-import") (part "M02LOCK"))
    )
    (comp (ref "SOUT5")
      (value "M02LOCK")
      (footprint "eagle-import:1X02_LOCK")
      (libsource (lib "eagle-import") (part "M02LOCK"))
    )
    (comp (ref "SOUT6")
      (value "M02LOCK")
      (footprint "eagle-import:1X02_LOCK")
      (libsource (lib "eagle-import") (part "M02LOCK"))
    )
    (comp (ref "U$1")
      (value "2PIN_PWR4-8-16MM")
      (footprint "eagle-import:2PIN_HOLES_PWR")
      (libsource (lib "eagle-import") (part "2PIN_PWR4-8-16MM"))
    )
  )
  (nets
    (net (code "1") (name "/DATA_IN") (class "Default")
      (node (ref "CHIP_1") (pin "P1") (pinfunction "SIN_P1") (pintype "bidirectional"))
      (node (ref "INPUT") (pin "2") (pinfunction "2_2") (pintype "passive"))
    )
    (net (code "2") (name "/DATA_OUT") (class "Default")
      (node (ref "CHIP_6") (pin "P28") (pinfunction "SOUT_P28") (pintype "bidirectional"))
      (node (ref "OUTPUT") (pin "2") (pinfunction "2_2") (pintype "passive"))
      (node (ref "SOUT6") (pin "1") (pinfunction "1_1") (pintype "passive"))
    )
    (net (code "3") (name "/GSCLK") (class "Default")
      (node (ref "CHIP_1") (pin "P55") (pinfunction "GSCLK_P55") (pintype "bidirectional"))
      (node (ref "CHIP_2") (pin "P55") (pinfunction "GSCLK_P55") (pintype "bidirectional"))
      (node (ref "CHIP_3") (pin "P55") (pinfunction "GSCLK_P55") (pintype "bidirectional"))
      (node (ref "CHIP_4") (pin "P55") (pinfunction "GSCLK_P55") (pintype "bidirectional"))
      (node (ref "CHIP_5") (pin "P55") (pinfunction "GSCLK_P55") (pintype "bidirectional"))
      (node (ref "CHIP_6") (pin "P55") (pinfunction "GSCLK_P55") (pintype "bidirectional"))
      (node (ref "INPUT") (pin "5") (pinfunction "5_5") (pintype "passive"))
      (node (ref "OUTPUT") (pin "5") (pinfunction "5_5") (pintype "passive"))
    )
    (net (code "4") (name "/LAT") (class "Default")
      (node (ref "CHIP_1") (pin "P3") (pinfunction "LAT_P3") (pintype "bidirectional"))
      (node (ref "CHIP_2") (pin "P3") (pinfunction "LAT_P3") (pintype "bidirectional"))
      (node (ref "CHIP_3") (pin "P3") (pinfunction "LAT_P3") (pintype "bidirectional"))
      (node (ref "CHIP_4") (pin "P3") (pinfunction "LAT_P3") (pintype "bidirectional"))
      (node (ref "CHIP_5") (pin "P3") (pinfunction "LAT_P3") (pintype "bidirectional"))
      (node (ref "CHIP_6") (pin "P3") (pinfunction "LAT_P3") (pintype "bidirectional"))
      (node (ref "INPUT") (pin "4") (pinfunction "4_4") (pintype "passive"))
      (node (ref "OUTPUT") (pin "4") (pinfunction "4_4") (pintype "passive"))
    )
    (net (code "5") (name "/SCLK") (class "Default")
      (node (ref "CHIP_1") (pin "P2") (pinfunction "SCLK_P2") (pintype "bidirectional"))
      (node (ref "CHIP_2") (pin "P2") (pinfunction "SCLK_P2") (pintype "bidirectional"))
      (node (ref "CHIP_3") (pin "P2") (pinfunction "SCLK_P2") (pintype "bidirectional"))
      (node (ref "CHIP_4") (pin "P2") (pinfunction "SCLK_P2") (pintype "bidirectional"))
      (node (ref "CHIP_5") (pin "P2") (pinfunction "SCLK_P2") (pintype "bidirectional"))
      (node (ref "CHIP_6") (pin "P2") (pinfunction "SCLK_P2") (pintype "bidirectional"))
      (node (ref "INPUT") (pin "3") (pinfunction "3_3") (pintype "passive"))
      (node (ref "OUTPUT") (pin "3") (pinfunction "3_3") (pintype "passive"))
    )
    (net (code "6") (name "GND") (class "Default")
      (node (ref "C1") (pin "1") (pinfunction "1_1") (pintype "passive"))
      (node (ref "C2") (pin "1") (pinfunction "1_1") (pintype "passive"))
      (node (ref "C3") (pin "1") (pinfunction "1_1") (pintype "passive"))
      (node (ref "C4") (pin "1") (pinfunction "1_1") (pintype "passive"))
      (node (ref "C5") (pin "1") (pinfunction "1_1") (pintype "passive"))
      (node (ref "C6") (pin "1") (pinfunction "1_1") (pintype "passive"))
      (node (ref "CHIP_1") (pin "P29") (pinfunction "GND2_P29") (pintype "bidirectional"))
      (node (ref "CHIP_1") (pin "P56") (pinfunction "GND_P56") (pintype "bidirectional"))
      (node (ref "CHIP_2") (pin "P29") (pinfunction "GND2_P29") (pintype "bidirectional"))
      (node (ref "CHIP_2") (pin "P56") (pinfunction "GND_P56") (pintype "bidirectional"))
      (node (ref "CHIP_3") (pin "P29") (pinfunction "GND2_P29") (pintype "bidirectional"))
      (node (ref "CHIP_3") (pin "P56") (pinfunction "GND_P56") (pintype "bidirectional"))
      (node (ref "CHIP_4") (pin "P29") (pinfunction "GND2_P29") (pintype "bidirectional"))
      (node (ref "CHIP_4") (pin "P56") (pinfunction "GND_P56") (pintype "bidirectional"))
      (node (ref "CHIP_5") (pin "P29") (pinfunction "GND2_P29") (pintype "bidirectional"))
      (node (ref "CHIP_5") (pin "P56") (pinfunction "GND_P56") (pintype "bidirectional"))
      (node (ref "CHIP_6") (pin "P29") (pinfunction "GND2_P29") (pintype "bidirectional"))
      (node (ref "CHIP_6") (pin "P56") (pinfunction "GND_P56") (pintype "bidirectional"))
      (node (ref "INPUT") (pin "1") (pinfunction "1_1") (pintype "passive"))
      (node (ref "OUTPUT") (pin "1") (pinfunction "1_1") (pintype "passive"))
      (node (ref "SOUT1") (pin "2") (pinfunction "2_2") (pintype "passive"))
      (node (ref "SOUT2") (pin "2") (pinfunction "2_2") (pintype "passive"))
      (node (ref "SOUT3") (pin "2") (pinfunction "2_2") (pintype "passive"))
      (node (ref "SOUT4") (pin "2") (pinfunction "2_2") (pintype "passive"))
      (node (ref "SOUT5") (pin "2") (pinfunction "2_2") (pintype "passive"))
      (node (ref "SOUT6") (pin "2") (pinfunction "2_2") (pintype "passive"))
      (node (ref "U$1") (pin "P$1") (pinfunction "GND_P$1") (pintype "bidirectional"))
    )
    (net (code "7") (name "Net-(CHIP_1-B0)") (class "Default")
      (node (ref "CHIP_1") (pin "P7") (pinfunction "B0_P7") (pintype "bidirectional"))
      (node (ref "D58") (pin "4") (pinfunction "BLUE_CATHODE_4") (pintype "bidirectional"))
    )
    (net (code "8") (name "Net-(CHIP_1-B1)") (class "Default")
      (node (ref "CHIP_1") (pin "P13") (pinfunction "B1_P13") (pintype "bidirectional"))
      (node (ref "D59") (pin "4") (pinfunction "BLUE_CATHODE_4") (pintype "bidirectional"))
    )
    (net (code "9") (name "Net-(CHIP_1-B2)") (class "Default")
      (node (ref "CHIP_1") (pin "P16") (pinfunction "B2_P16") (pintype "bidirectional"))
      (node (ref "D55") (pin "4") (pinfunction "BLUE_CATHODE_4") (pintype "bidirectional"))
    )
    (net (code "10") (name "Net-(CHIP_1-B3)") (class "Default")
      (node (ref "CHIP_1") (pin "P22") (pinfunction "B3_P22") (pintype "bidirectional"))
      (node (ref "D63") (pin "4") (pinfunction "BLUE_CATHODE_4") (pintype "bidirectional"))
    )
    (net (code "11") (name "Net-(CHIP_1-B4)") (class "Default")
      (node (ref "CHIP_1") (pin "P4") (pinfunction "B4_P4") (pintype "bidirectional"))
      (node (ref "D64") (pin "4") (pinfunction "BLUE_CATHODE_4") (pintype "bidirectional"))
    )
    (net (code "12") (name "Net-(CHIP_1-B5)") (class "Default")
      (node (ref "CHIP_1") (pin "P10") (pinfunction "B5_P10") (pintype "bidirectional"))
      (node (ref "D56") (pin "4") (pinfunction "BLUE_CATHODE_4") (pintype "bidirectional"))
    )
    (net (code "13") (name "Net-(CHIP_1-B6)") (class "Default")
      (node (ref "CHIP_1") (pin "P19") (pinfunction "B6_P19") (pintype "bidirectional"))
      (node (ref "D51") (pin "4") (pinfunction "BLUE_CATHODE_4") (pintype "bidirectional"))
    )
    (net (code "14") (name "Net-(CHIP_1-B7)") (class "Default")
      (node (ref "CHIP_1") (pin "P25") (pinfunction "B7_P25") (pintype "bidirectional"))
      (node (ref "D60") (pin "4") (pinfunction "BLUE_CATHODE_4") (pintype "bidirectional"))
    )
    (net (code "15") (name "Net-(CHIP_1-B8)") (class "Default")
      (node (ref "CHIP_1") (pin "P53") (pinfunction "B8_P53") (pintype "bidirectional"))
      (node (ref "D53") (pin "4") (pinfunction "BLUE_CATHODE_4") (pintype "bidirectional"))
    )
    (net (code "16") (name "Net-(CHIP_1-B9)") (class "Default")
      (node (ref "CHIP_1") (pin "P47") (pinfunction "B9_P47") (pintype "bidirectional"))
      (node (ref "D54") (pin "4") (pinfunction "BLUE_CATHODE_4") (pintype "bidirectional"))
    )
    (net (code "17") (name "Net-(CHIP_1-B10)") (class "Default")
      (node (ref "CHIP_1") (pin "P38") (pinfunction "B10_P38") (pintype "bidirectional"))
      (node (ref "D50") (pin "4") (pinfunction "BLUE_CATHODE_4") (pintype "bidirectional"))
    )
    (net (code "18") (name "Net-(CHIP_1-B11)") (class "Default")
      (node (ref "CHIP_1") (pin "P32") (pinfunction "B11_P32") (pintype "bidirectional"))
      (node (ref "D52") (pin "4") (pinfunction "BLUE_CATHODE_4") (pintype "bidirectional"))
    )
    (net (code "19") (name "Net-(CHIP_1-B12)") (class "Default")
      (node (ref "CHIP_1") (pin "P50") (pinfunction "B12_P50") (pintype "bidirectional"))
      (node (ref "D62") (pin "4") (pinfunction "BLUE_CATHODE_4") (pintype "bidirectional"))
    )
    (net (code "20") (name "Net-(CHIP_1-B13)") (class "Default")
      (node (ref "CHIP_1") (pin "P44") (pinfunction "B13_P44") (pintype "bidirectional"))
      (node (ref "D61") (pin "4") (pinfunction "BLUE_CATHODE_4") (pintype "bidirectional"))
    )
    (net (code "21") (name "Net-(CHIP_1-B14)") (class "Default")
      (node (ref "CHIP_1") (pin "P41") (pinfunction "B14_P41") (pintype "bidirectional"))
      (node (ref "D49") (pin "4") (pinfunction "BLUE_CATHODE_4") (pintype "bidirectional"))
    )
    (net (code "22") (name "Net-(CHIP_1-B15)") (class "Default")
      (node (ref "CHIP_1") (pin "P35") (pinfunction "B15_P35") (pintype "bidirectional"))
      (node (ref "D57") (pin "4") (pinfunction "BLUE_CATHODE_4") (pintype "bidirectional"))
    )
    (net (code "23") (name "Net-(CHIP_1-G0)") (class "Default")
      (node (ref "CHIP_1") (pin "P9") (pinfunction "G0_P9") (pintype "bidirectional"))
      (node (ref "D58") (pin "1") (pinfunction "GREEN_CATHODE_1") (pintype "bidirectional"))
    )
    (net (code "24") (name "Net-(CHIP_1-G1)") (class "Default")
      (node (ref "CHIP_1") (pin "P15") (pinfunction "G1_P15") (pintype "bidirectional"))
      (node (ref "D59") (pin "1") (pinfunction "GREEN_CATHODE_1") (pintype "bidirectional"))
    )
    (net (code "25") (name "Net-(CHIP_1-G2)") (class "Default")
      (node (ref "CHIP_1") (pin "P18") (pinfunction "G2_P18") (pintype "bidirectional"))
      (node (ref "D55") (pin "1") (pinfunction "GREEN_CATHODE_1") (pintype "bidirectional"))
    )
    (net (code "26") (name "Net-(CHIP_1-G3)") (class "Default")
      (node (ref "CHIP_1") (pin "P24") (pinfunction "G3_P24") (pintype "bidirectional"))
      (node (ref "D63") (pin "1") (pinfunction "GREEN_CATHODE_1") (pintype "bidirectional"))
    )
    (net (code "27") (name "Net-(CHIP_1-G4)") (class "Default")
      (node (ref "CHIP_1") (pin "P6") (pinfunction "G4_P6") (pintype "bidirectional"))
      (node (ref "D64") (pin "1") (pinfunction "GREEN_CATHODE_1") (pintype "bidirectional"))
    )
    (net (code "28") (name "Net-(CHIP_1-G5)") (class "Default")
      (node (ref "CHIP_1") (pin "P12") (pinfunction "G5_P12") (pintype "bidirectional"))
      (node (ref "D56") (pin "1") (pinfunction "GREEN_CATHODE_1") (pintype "bidirectional"))
    )
    (net (code "29") (name "Net-(CHIP_1-G6)") (class "Default")
      (node (ref "CHIP_1") (pin "P21") (pinfunction "G6_P21") (pintype "bidirectional"))
      (node (ref "D51") (pin "1") (pinfunction "GREEN_CATHODE_1") (pintype "bidirectional"))
    )
    (net (code "30") (name "Net-(CHIP_1-G7)") (class "Default")
      (node (ref "CHIP_1") (pin "P27") (pinfunction "G7_P27") (pintype "bidirectional"))
      (node (ref "D60") (pin "1") (pinfunction "GREEN_CATHODE_1") (pintype "bidirectional"))
    )
    (net (code "31") (name "Net-(CHIP_1-G8)") (class "Default")
      (node (ref "CHIP_1") (pin "P51") (pinfunction "G8_P51") (pintype "bidirectional"))
      (node (ref "D53") (pin "1") (pinfunction "GREEN_CATHODE_1") (pintype "bidirectional"))
    )
    (net (code "32") (name "Net-(CHIP_1-G9)") (class "Default")
      (node (ref "CHIP_1") (pin "P45") (pinfunction "G9_P45") (pintype "bidirectional"))
      (node (ref "D54") (pin "1") (pinfunction "GREEN_CATHODE_1") (pintype "bidirectional"))
    )
    (net (code "33") (name "Net-(CHIP_1-G10)") (class "Default")
      (node (ref "CHIP_1") (pin "P36") (pinfunction "G10_P36") (pintype "bidirectional"))
      (node (ref "D50") (pin "1") (pinfunction "GREEN_CATHODE_1") (pintype "bidirectional"))
    )
    (net (code "34") (name "Net-(CHIP_1-G11)") (class "Default")
      (node (ref "CHIP_1") (pin "P30") (pinfunction "G11_P30") (pintype "bidirectional"))
      (node (ref "D52") (pin "1") (pinfunction "GREEN_CATHODE_1") (pintype "bidirectional"))
    )
    (net (code "35") (name "Net-(CHIP_1-G12)") (class "Default")
      (node (ref "CHIP_1") (pin "P48") (pinfunction "G12_P48") (pintype "bidirectional"))
      (node (ref "D62") (pin "1") (pinfunction "GREEN_CATHODE_1") (pintype "bidirectional"))
    )
    (net (code "36") (name "Net-(CHIP_1-G13)") (class "Default")
      (node (ref "CHIP_1") (pin "P42") (pinfunction "G13_P42") (pintype "bidirectional"))
      (node (ref "D61") (pin "1") (pinfunction "GREEN_CATHODE_1") (pintype "bidirectional"))
    )
    (net (code "37") (name "Net-(CHIP_1-G14)") (class "Default")
      (node (ref "CHIP_1") (pin "P39") (pinfunction "G14_P39") (pintype "bidirectional"))
      (node (ref "D49") (pin "1") (pinfunction "GREEN_CATHODE_1") (pintype "bidirectional"))
    )
    (net (code "38") (name "Net-(CHIP_1-G15)") (class "Default")
      (node (ref "CHIP_1") (pin "P33") (pinfunction "G15_P33") (pintype "bidirectional"))
      (node (ref "D57") (pin "1") (pinfunction "GREEN_CATHODE_1") (pintype "bidirectional"))
    )
    (net (code "39") (name "Net-(CHIP_1-R0)") (class "Default")
      (node (ref "CHIP_1") (pin "P8") (pinfunction "R0_P8") (pintype "bidirectional"))
      (node (ref "D58") (pin "3") (pinfunction "RED_CATHODE_3") (pintype "bidirectional"))
    )
    (net (code "40") (name "Net-(CHIP_1-R1)") (class "Default")
      (node (ref "CHIP_1") (pin "P14") (pinfunction "R1_P14") (pintype "bidirectional"))
      (node (ref "D59") (pin "3") (pinfunction "RED_CATHODE_3") (pintype "bidirectional"))
    )
    (net (code "41") (name "Net-(CHIP_1-R2)") (class "Default")
      (node (ref "CHIP_1") (pin "P17") (pinfunction "R2_P17") (pintype "bidirectional"))
      (node (ref "D55") (pin "3") (pinfunction "RED_CATHODE_3") (pintype "bidirectional"))
    )
    (net (code "42") (name "Net-(CHIP_1-R3)") (class "Default")
      (node (ref "CHIP_1") (pin "P23") (pinfunction "R3_P23") (pintype "bidirectional"))
      (node (ref "D63") (pin "3") (pinfunction "RED_CATHODE_3") (pintype "bidirectional"))
    )
    (net (code "43") (name "Net-(CHIP_1-R4)") (class "Default")
      (node (ref "CHIP_1") (pin "P5") (pinfunction "R4_P5") (pintype "bidirectional"))
      (node (ref "D64") (pin "3") (pinfunction "RED_CATHODE_3") (pintype "bidirectional"))
    )
    (net (code "44") (name "Net-(CHIP_1-R5)") (class "Default")
      (node (ref "CHIP_1") (pin "P11") (pinfunction "R5_P11") (pintype "bidirectional"))
      (node (ref "D56") (pin "3") (pinfunction "RED_CATHODE_3") (pintype "bidirectional"))
    )
    (net (code "45") (name "Net-(CHIP_1-R6)") (class "Default")
      (node (ref "CHIP_1") (pin "P20") (pinfunction "R6_P20") (pintype "bidirectional"))
      (node (ref "D51") (pin "3") (pinfunction "RED_CATHODE_3") (pintype "bidirectional"))
    )
    (net (code "46") (name "Net-(CHIP_1-R7)") (class "Default")
      (node (ref "CHIP_1") (pin "P26") (pinfunction "R7_P26") (pintype "bidirectional"))
      (node (ref "D60") (pin "3") (pinfunction "RED_CATHODE_3") (pintype "bidirectional"))
    )
    (net (code "47") (name "Net-(CHIP_1-R8)") (class "Default")
      (node (ref "CHIP_1") (pin "P52") (pinfunction "R8_P52") (pintype "bidirectional"))
      (node (ref "D53") (pin "3") (pinfunction "RED_CATHODE_3") (pintype "bidirectional"))
    )
    (net (code "48") (name "Net-(CHIP_1-R9)") (class "Default")
      (node (ref "CHIP_1") (pin "P46") (pinfunction "R9_P46") (pintype "bidirectional"))
      (node (ref "D54") (pin "3") (pinfunction "RED_CATHODE_3") (pintype "bidirectional"))
    )
    (net (code "49") (name "Net-(CHIP_1-R10)") (class "Default")
      (node (ref "CHIP_1") (pin "P37") (pinfunction "R10_P37") (pintype "bidirectional"))
      (node (ref "D50") (pin "3") (pinfunction "RED_CATHODE_3") (pintype "bidirectional"))
    )
    (net (code "50") (name "Net-(CHIP_1-R11)") (class "Default")
      (node (ref "CHIP_1") (pin "P31") (pinfunction "R11_P31") (pintype "bidirectional"))
      (node (ref "D52") (pin "3") (pinfunction "RED_CATHODE_3") (pintype "bidirectional"))
    )
    (net (code "51") (name "Net-(CHIP_1-R12)") (class "Default")
      (node (ref "CHIP_1") (pin "P49") (pinfunction "R12_P49") (pintype "bidirectional"))
      (node (ref "D62") (pin "3") (pinfunction "RED_CATHODE_3") (pintype "bidirectional"))
    )
    (net (code "52") (name "Net-(CHIP_1-R13)") (class "Default")
      (node (ref "CHIP_1") (pin "P43") (pinfunction "R13_P43") (pintype "bidirectional"))
      (node (ref "D61") (pin "3") (pinfunction "RED_CATHODE_3") (pintype "bidirectional"))
    )
    (net (code "53") (name "Net-(CHIP_1-R14)") (class "Default")
      (node (ref "CHIP_1") (pin "P40") (pinfunction "R14_P40") (pintype "bidirectional"))
      (node (ref "D49") (pin "3") (pinfunction "RED_CATHODE_3") (pintype "bidirectional"))
    )
    (net (code "54") (name "Net-(CHIP_1-R15)") (class "Default")
      (node (ref "CHIP_1") (pin "P34") (pinfunction "R15_P34") (pintype "bidirectional"))
      (node (ref "D57") (pin "3") (pinfunction "RED_CATHODE_3") (pintype "bidirectional"))
    )
    (net (code "55") (name "Net-(CHIP_1-SOUT)") (class "Default")
      (node (ref "CHIP_1") (pin "P28") (pinfunction "SOUT_P28") (pintype "bidirectional"))
      (node (ref "CHIP_2") (pin "P1") (pinfunction "SIN_P1") (pintype "bidirectional"))
      (node (ref "SOUT1") (pin "1") (pinfunction "1_1") (pintype "passive"))
    )
    (net (code "56") (name "Net-(CHIP_2-B0)") (class "Default")
      (node (ref "CHIP_2") (pin "P7") (pinfunction "B0_P7") (pintype "bidirectional"))
      (node (ref "D74") (pin "4") (pinfunction "BLUE_CATHODE_4") (pintype "bidirectional"))
    )
    (net (code "57") (name "Net-(CHIP_2-B1)") (class "Default")
      (node (ref "CHIP_2") (pin "P13") (pinfunction "B1_P13") (pintype "bidirectional"))
      (node (ref "D75") (pin "4") (pinfunction "BLUE_CATHODE_4") (pintype "bidirectional"))
    )
    (net (code "58") (name "Net-(CHIP_2-B2)") (class "Default")
      (node (ref "CHIP_2") (pin "P16") (pinfunction "B2_P16") (pintype "bidirectional"))
      (node (ref "D71") (pin "4") (pinfunction "BLUE_CATHODE_4") (pintype "bidirectional"))
    )
    (net (code "59") (name "Net-(CHIP_2-B3)") (class "Default")
      (node (ref "CHIP_2") (pin "P22") (pinfunction "B3_P22") (pintype "bidirectional"))
      (node (ref "D79") (pin "4") (pinfunction "BLUE_CATHODE_4") (pintype "bidirectional"))
    )
    (net (code "60") (name "Net-(CHIP_2-B4)") (class "Default")
      (node (ref "CHIP_2") (pin "P4") (pinfunction "B4_P4") (pintype "bidirectional"))
      (node (ref "D80") (pin "4") (pinfunction "BLUE_CATHODE_4") (pintype "bidirectional"))
    )
    (net (code "61") (name "Net-(CHIP_2-B5)") (class "Default")
      (node (ref "CHIP_2") (pin "P10") (pinfunction "B5_P10") (pintype "bidirectional"))
      (node (ref "D72") (pin "4") (pinfunction "BLUE_CATHODE_4") (pintype "bidirectional"))
    )
    (net (code "62") (name "Net-(CHIP_2-B6)") (class "Default")
      (node (ref "CHIP_2") (pin "P19") (pinfunction "B6_P19") (pintype "bidirectional"))
      (node (ref "D67") (pin "4") (pinfunction "BLUE_CATHODE_4") (pintype "bidirectional"))
    )
    (net (code "63") (name "Net-(CHIP_2-B7)") (class "Default")
      (node (ref "CHIP_2") (pin "P25") (pinfunction "B7_P25") (pintype "bidirectional"))
      (node (ref "D76") (pin "4") (pinfunction "BLUE_CATHODE_4") (pintype "bidirectional"))
    )
    (net (code "64") (name "Net-(CHIP_2-B8)") (class "Default")
      (node (ref "CHIP_2") (pin "P53") (pinfunction "B8_P53") (pintype "bidirectional"))
      (node (ref "D69") (pin "4") (pinfunction "BLUE_CATHODE_4") (pintype "bidirectional"))
    )
    (net (code "65") (name "Net-(CHIP_2-B9)") (class "Default")
      (node (ref "CHIP_2") (pin "P47") (pinfunction "B9_P47") (pintype "bidirectional"))
      (node (ref "D70") (pin "4") (pinfunction "BLUE_CATHODE_4") (pintype "bidirectional"))
    )
    (net (code "66") (name "Net-(CHIP_2-B10)") (class "Default")
      (node (ref "CHIP_2") (pin "P38") (pinfunction "B10_P38") (pintype "bidirectional"))
      (node (ref "D66") (pin "4") (pinfunction "BLUE_CATHODE_4") (pintype "bidirectional"))
    )
    (net (code "67") (name "Net-(CHIP_2-B11)") (class "Default")
      (node (ref "CHIP_2") (pin "P32") (pinfunction "B11_P32") (pintype "bidirectional"))
      (node (ref "D68") (pin "4") (pinfunction "BLUE_CATHODE_4") (pintype "bidirectional"))
    )
    (net (code "68") (name "Net-(CHIP_2-B12)") (class "Default")
      (node (ref "CHIP_2") (pin "P50") (pinfunction "B12_P50") (pintype "bidirectional"))
      (node (ref "D78") (pin "4") (pinfunction "BLUE_CATHODE_4") (pintype "bidirectional"))
    )
    (net (code "69") (name "Net-(CHIP_2-B13)") (class "Default")
      (node (ref "CHIP_2") (pin "P44") (pinfunction "B13_P44") (pintype "bidirectional"))
      (node (ref "D77") (pin "4") (pinfunction "BLUE_CATHODE_4") (pintype "bidirectional"))
    )
    (net (code "70") (name "Net-(CHIP_2-B14)") (class "Default")
      (node (ref "CHIP_2") (pin "P41") (pinfunction "B14_P41") (pintype "bidirectional"))
      (node (ref "D65") (pin "4") (pinfunction "BLUE_CATHODE_4") (pintype "bidirectional"))
    )
    (net (code "71") (name "Net-(CHIP_2-B15)") (class "Default")
      (node (ref "CHIP_2") (pin "P35") (pinfunction "B15_P35") (pintype "bidirectional"))
      (node (ref "D73") (pin "4") (pinfunction "BLUE_CATHODE_4") (pintype "bidirectional"))
    )
    (net (code "72") (name "Net-(CHIP_2-G0)") (class "Default")
      (node (ref "CHIP_2") (pin "P9") (pinfunction "G0_P9") (pintype "bidirectional"))
      (node (ref "D74") (pin "1") (pinfunction "GREEN_CATHODE_1") (pintype "bidirectional"))
    )
    (net (code "73") (name "Net-(CHIP_2-G1)") (class "Default")
      (node (ref "CHIP_2") (pin "P15") (pinfunction "G1_P15") (pintype "bidirectional"))
      (node (ref "D75") (pin "1") (pinfunction "GREEN_CATHODE_1") (pintype "bidirectional"))
    )
    (net (code "74") (name "Net-(CHIP_2-G2)") (class "Default")
      (node (ref "CHIP_2") (pin "P18") (pinfunction "G2_P18") (pintype "bidirectional"))
      (node (ref "D71") (pin "1") (pinfunction "GREEN_CATHODE_1") (pintype "bidirectional"))
    )
    (net (code "75") (name "Net-(CHIP_2-G3)") (class "Default")
      (node (ref "CHIP_2") (pin "P24") (pinfunction "G3_P24") (pintype "bidirectional"))
      (node (ref "D79") (pin "1") (pinfunction "GREEN_CATHODE_1") (pintype "bidirectional"))
    )
    (net (code "76") (name "Net-(CHIP_2-G4)") (class "Default")
      (node (ref "CHIP_2") (pin "P6") (pinfunction "G4_P6") (pintype "bidirectional"))
      (node (ref "D80") (pin "1") (pinfunction "GREEN_CATHODE_1") (pintype "bidirectional"))
    )
    (net (code "77") (name "Net-(CHIP_2-G5)") (class "Default")
      (node (ref "CHIP_2") (pin "P12") (pinfunction "G5_P12") (pintype "bidirectional"))
      (node (ref "D72") (pin "1") (pinfunction "GREEN_CATHODE_1") (pintype "bidirectional"))
    )
    (net (code "78") (name "Net-(CHIP_2-G6)") (class "Default")
      (node (ref "CHIP_2") (pin "P21") (pinfunction "G6_P21") (pintype "bidirectional"))
      (node (ref "D67") (pin "1") (pinfunction "GREEN_CATHODE_1") (pintype "bidirectional"))
    )
    (net (code "79") (name "Net-(CHIP_2-G7)") (class "Default")
      (node (ref "CHIP_2") (pin "P27") (pinfunction "G7_P27") (pintype "bidirectional"))
      (node (ref "D76") (pin "1") (pinfunction "GREEN_CATHODE_1") (pintype "bidirectional"))
    )
    (net (code "80") (name "Net-(CHIP_2-G8)") (class "Default")
      (node (ref "CHIP_2") (pin "P51") (pinfunction "G8_P51") (pintype "bidirectional"))
      (node (ref "D69") (pin "1") (pinfunction "GREEN_CATHODE_1") (pintype "bidirectional"))
    )
    (net (code "81") (name "Net-(CHIP_2-G9)") (class "Default")
      (node (ref "CHIP_2") (pin "P45") (pinfunction "G9_P45") (pintype "bidirectional"))
      (node (ref "D70") (pin "1") (pinfunction "GREEN_CATHODE_1") (pintype "bidirectional"))
    )
    (net (code "82") (name "Net-(CHIP_2-G10)") (class "Default")
      (node (ref "CHIP_2") (pin "P36") (pinfunction "G10_P36") (pintype "bidirectional"))
      (node (ref "D66") (pin "1") (pinfunction "GREEN_CATHODE_1") (pintype "bidirectional"))
    )
    (net (code "83") (name "Net-(CHIP_2-G11)") (class "Default")
      (node (ref "CHIP_2") (pin "P30") (pinfunction "G11_P30") (pintype "bidirectional"))
      (node (ref "D68") (pin "1") (pinfunction "GREEN_CATHODE_1") (pintype "bidirectional"))
    )
    (net (code "84") (name "Net-(CHIP_2-G12)") (class "Default")
      (node (ref "CHIP_2") (pin "P48") (pinfunction "G12_P48") (pintype "bidirectional"))
      (node (ref "D78") (pin "1") (pinfunction "GREEN_CATHODE_1") (pintype "bidirectional"))
    )
    (net (code "85") (name "Net-(CHIP_2-G13)") (class "Default")
      (node (ref "CHIP_2") (pin "P42") (pinfunction "G13_P42") (pintype "bidirectional"))
      (node (ref "D77") (pin "1") (pinfunction "GREEN_CATHODE_1") (pintype "bidirectional"))
    )
    (net (code "86") (name "Net-(CHIP_2-G14)") (class "Default")
      (node (ref "CHIP_2") (pin "P39") (pinfunction "G14_P39") (pintype "bidirectional"))
      (node (ref "D65") (pin "1") (pinfunction "GREEN_CATHODE_1") (pintype "bidirectional"))
    )
    (net (code "87") (name "Net-(CHIP_2-G15)") (class "Default")
      (node (ref "CHIP_2") (pin "P33") (pinfunction "G15_P33") (pintype "bidirectional"))
      (node (ref "D73") (pin "1") (pinfunction "GREEN_CATHODE_1") (pintype "bidirectional"))
    )
    (net (code "88") (name "Net-(CHIP_2-R0)") (class "Default")
      (node (ref "CHIP_2") (pin "P8") (pinfunction "R0_P8") (pintype "bidirectional"))
      (node (ref "D74") (pin "3") (pinfunction "RED_CATHODE_3") (pintype "bidirectional"))
    )
    (net (code "89") (name "Net-(CHIP_2-R1)") (class "Default")
      (node (ref "CHIP_2") (pin "P14") (pinfunction "R1_P14") (pintype "bidirectional"))
      (node (ref "D75") (pin "3") (pinfunction "RED_CATHODE_3") (pintype "bidirectional"))
    )
    (net (code "90") (name "Net-(CHIP_2-R2)") (class "Default")
      (node (ref "CHIP_2") (pin "P17") (pinfunction "R2_P17") (pintype "bidirectional"))
      (node (ref "D71") (pin "3") (pinfunction "RED_CATHODE_3") (pintype "bidirectional"))
    )
    (net (code "91") (name "Net-(CHIP_2-R3)") (class "Default")
      (node (ref "CHIP_2") (pin "P23") (pinfunction "R3_P23") (pintype "bidirectional"))
      (node (ref "D79") (pin "3") (pinfunction "RED_CATHODE_3") (pintype "bidirectional"))
    )
    (net (code "92") (name "Net-(CHIP_2-R4)") (class "Default")
      (node (ref "CHIP_2") (pin "P5") (pinfunction "R4_P5") (pintype "bidirectional"))
      (node (ref "D80") (pin "3") (pinfunction "RED_CATHODE_3") (pintype "bidirectional"))
    )
    (net (code "93") (name "Net-(CHIP_2-R5)") (class "Default")
      (node (ref "CHIP_2") (pin "P11") (pinfunction "R5_P11") (pintype "bidirectional"))
      (node (ref "D72") (pin "3") (pinfunction "RED_CATHODE_3") (pintype "bidirectional"))
    )
    (net (code "94") (name "Net-(CHIP_2-R6)") (class "Default")
      (node (ref "CHIP_2") (pin "P20") (pinfunction "R6_P20") (pintype "bidirectional"))
      (node (ref "D67") (pin "3") (pinfunction "RED_CATHODE_3") (pintype "bidirectional"))
    )
    (net (code "95") (name "Net-(CHIP_2-R7)") (class "Default")
      (node (ref "CHIP_2") (pin "P26") (pinfunction "R7_P26") (pintype "bidirectional"))
      (node (ref "D76") (pin "3") (pinfunction "RED_CATHODE_3") (pintype "bidirectional"))
    )
    (net (code "96") (name "Net-(CHIP_2-R8)") (class "Default")
      (node (ref "CHIP_2") (pin "P52") (pinfunction "R8_P52") (pintype "bidirectional"))
      (node (ref "D69") (pin "3") (pinfunction "RED_CATHODE_3") (pintype "bidirectional"))
    )
    (net (code "97") (name "Net-(CHIP_2-R9)") (class "Default")
      (node (ref "CHIP_2") (pin "P46") (pinfunction "R9_P46") (pintype "bidirectional"))
      (node (ref "D70") (pin "3") (pinfunction "RED_CATHODE_3") (pintype "bidirectional"))
    )
    (net (code "98") (name "Net-(CHIP_2-R10)") (class "Default")
      (node (ref "CHIP_2") (pin "P37") (pinfunction "R10_P37") (pintype "bidirectional"))
      (node (ref "D66") (pin "3") (pinfunction "RED_CATHODE_3") (pintype "bidirectional"))
    )
    (net (code "99") (name "Net-(CHIP_2-R11)") (class "Default")
      (node (ref "CHIP_2") (pin "P31") (pinfunction "R11_P31") (pintype "bidirectional"))
      (node (ref "D68") (pin "3") (pinfunction "RED_CATHODE_3") (pintype "bidirectional"))
    )
    (net (code "100") (name "Net-(CHIP_2-R12)") (class "Default")
      (node (ref "CHIP_2") (pin "P49") (pinfunction "R12_P49") (pintype "bidirectional"))
      (node (ref "D78") (pin "3") (pinfunction "RED_CATHODE_3") (pintype "bidirectional"))
    )
    (net (code "101") (name "Net-(CHIP_2-R13)") (class "Default")
      (node (ref "CHIP_2") (pin "P43") (pinfunction "R13_P43") (pintype "bidirectional"))
      (node (ref "D77") (pin "3") (pinfunction "RED_CATHODE_3") (pintype "bidirectional"))
    )
    (net (code "102") (name "Net-(CHIP_2-R14)") (class "Default")
      (node (ref "CHIP_2") (pin "P40") (pinfunction "R14_P40") (pintype "bidirectional"))
      (node (ref "D65") (pin "3") (pinfunction "RED_CATHODE_3") (pintype "bidirectional"))
    )
    (net (code "103") (name "Net-(CHIP_2-R15)") (class "Default")
      (node (ref "CHIP_2") (pin "P34") (pinfunction "R15_P34") (pintype "bidirectional"))
      (node (ref "D73") (pin "3") (pinfunction "RED_CATHODE_3") (pintype "bidirectional"))
    )
    (net (code "104") (name "Net-(CHIP_2-SOUT)") (class "Default")
      (node (ref "CHIP_2") (pin "P28") (pinfunction "SOUT_P28") (pintype "bidirectional"))
      (node (ref "CHIP_3") (pin "P1") (pinfunction "SIN_P1") (pintype "bidirectional"))
      (node (ref "SOUT2") (pin "1") (pinfunction "1_1") (pintype "passive"))
    )
    (net (code "105") (name "Net-(CHIP_3-B0)") (class "Default")
      (node (ref "CHIP_3") (pin "P7") (pinfunction "B0_P7") (pintype "bidirectional"))
      (node (ref "D90") (pin "4") (pinfunction "BLUE_CATHODE_4") (pintype "bidirectional"))
    )
    (net (code "106") (name "Net-(CHIP_3-B1)") (class "Default")
      (node (ref "CHIP_3") (pin "P13") (pinfunction "B1_P13") (pintype "bidirectional"))
      (node (ref "D91") (pin "4") (pinfunction "BLUE_CATHODE_4") (pintype "bidirectional"))
    )
    (net (code "107") (name "Net-(CHIP_3-B2)") (class "Default")
      (node (ref "CHIP_3") (pin "P16") (pinfunction "B2_P16") (pintype "bidirectional"))
      (node (ref "D87") (pin "4") (pinfunction "BLUE_CATHODE_4") (pintype "bidirectional"))
    )
    (net (code "108") (name "Net-(CHIP_3-B3)") (class "Default")
      (node (ref "CHIP_3") (pin "P22") (pinfunction "B3_P22") (pintype "bidirectional"))
      (node (ref "D95") (pin "4") (pinfunction "BLUE_CATHODE_4") (pintype "bidirectional"))
    )
    (net (code "109") (name "Net-(CHIP_3-B4)") (class "Default")
      (node (ref "CHIP_3") (pin "P4") (pinfunction "B4_P4") (pintype "bidirectional"))
      (node (ref "D96") (pin "4") (pinfunction "BLUE_CATHODE_4") (pintype "bidirectional"))
    )
    (net (code "110") (name "Net-(CHIP_3-B5)") (class "Default")
      (node (ref "CHIP_3") (pin "P10") (pinfunction "B5_P10") (pintype "bidirectional"))
      (node (ref "D88") (pin "4") (pinfunction "BLUE_CATHODE_4") (pintype "bidirectional"))
    )
    (net (code "111") (name "Net-(CHIP_3-B6)") (class "Default")
      (node (ref "CHIP_3") (pin "P19") (pinfunction "B6_P19") (pintype "bidirectional"))
      (node (ref "D83") (pin "4") (pinfunction "BLUE_CATHODE_4") (pintype "bidirectional"))
    )
    (net (code "112") (name "Net-(CHIP_3-B7)") (class "Default")
      (node (ref "CHIP_3") (pin "P25") (pinfunction "B7_P25") (pintype "bidirectional"))
      (node (ref "D92") (pin "4") (pinfunction "BLUE_CATHODE_4") (pintype "bidirectional"))
    )
    (net (code "113") (name "Net-(CHIP_3-B8)") (class "Default")
      (node (ref "CHIP_3") (pin "P53") (pinfunction "B8_P53") (pintype "bidirectional"))
      (node (ref "D85") (pin "4") (pinfunction "BLUE_CATHODE_4") (pintype "bidirectional"))
    )
    (net (code "114") (name "Net-(CHIP_3-B9)") (class "Default")
      (node (ref "CHIP_3") (pin "P47") (pinfunction "B9_P47") (pintype "bidirectional"))
      (node (ref "D86") (pin "4") (pinfunction "BLUE_CATHODE_4") (pintype "bidirectional"))
    )
    (net (code "115") (name "Net-(CHIP_3-B10)") (class "Default")
      (node (ref "CHIP_3") (pin "P38") (pinfunction "B10_P38") (pintype "bidirectional"))
      (node (ref "D82") (pin "4") (pinfunction "BLUE_CATHODE_4") (pintype "bidirectional"))
    )
    (net (code "116") (name "Net-(CHIP_3-B11)") (class "Default")
      (node (ref "CHIP_3") (pin "P32") (pinfunction "B11_P32") (pintype "bidirectional"))
      (node (ref "D84") (pin "4") (pinfunction "BLUE_CATHODE_4") (pintype "bidirectional"))
    )
    (net (code "117") (name "Net-(CHIP_3-B12)") (class "Default")
      (node (ref "CHIP_3") (pin "P50") (pinfunction "B12_P50") (pintype "bidirectional"))
      (node (ref "D94") (pin "4") (pinfunction "BLUE_CATHODE_4") (pintype "bidirectional"))
    )
    (net (code "118") (name "Net-(CHIP_3-B13)") (class "Default")
      (node (ref "CHIP_3") (pin "P44") (pinfunction "B13_P44") (pintype "bidirectional"))
      (node (ref "D93") (pin "4") (pinfunction "BLUE_CATHODE_4") (pintype "bidirectional"))
    )
    (net (code "119") (name "Net-(CHIP_3-B14)") (class "Default")
      (node (ref "CHIP_3") (pin "P41") (pinfunction "B14_P41") (pintype "bidirectional"))
      (node (ref "D81") (pin "4") (pinfunction "BLUE_CATHODE_4") (pintype "bidirectional"))
    )
    (net (code "120") (name "Net-(CHIP_3-B15)") (class "Default")
      (node (ref "CHIP_3") (pin "P35") (pinfunction "B15_P35") (pintype "bidirectional"))
      (node (ref "D89") (pin "4") (pinfunction "BLUE_CATHODE_4") (pintype "bidirectional"))
    )
    (net (code "121") (name "Net-(CHIP_3-G0)") (class "Default")
      (node (ref "CHIP_3") (pin "P9") (pinfunction "G0_P9") (pintype "bidirectional"))
      (node (ref "D90") (pin "1") (pinfunction "GREEN_CATHODE_1") (pintype "bidirectional"))
    )
    (net (code "122") (name "Net-(CHIP_3-G1)") (class "Default")
      (node (ref "CHIP_3") (pin "P15") (pinfunction "G1_P15") (pintype "bidirectional"))
      (node (ref "D91") (pin "1") (pinfunction "GREEN_CATHODE_1") (pintype "bidirectional"))
    )
    (net (code "123") (name "Net-(CHIP_3-G2)") (class "Default")
      (node (ref "CHIP_3") (pin "P18") (pinfunction "G2_P18") (pintype "bidirectional"))
      (node (ref "D87") (pin "1") (pinfunction "GREEN_CATHODE_1") (pintype "bidirectional"))
    )
    (net (code "124") (name "Net-(CHIP_3-G3)") (class "Default")
      (node (ref "CHIP_3") (pin "P24") (pinfunction "G3_P24") (pintype "bidirectional"))
      (node (ref "D95") (pin "1") (pinfunction "GREEN_CATHODE_1") (pintype "bidirectional"))
    )
    (net (code "125") (name "Net-(CHIP_3-G4)") (class "Default")
      (node (ref "CHIP_3") (pin "P6") (pinfunction "G4_P6") (pintype "bidirectional"))
      (node (ref "D96") (pin "1") (pinfunction "GREEN_CATHODE_1") (pintype "bidirectional"))
    )
    (net (code "126") (name "Net-(CHIP_3-G5)") (class "Default")
      (node (ref "CHIP_3") (pin "P12") (pinfunction "G5_P12") (pintype "bidirectional"))
      (node (ref "D88") (pin "1") (pinfunction "GREEN_CATHODE_1") (pintype "bidirectional"))
    )
    (net (code "127") (name "Net-(CHIP_3-G6)") (class "Default")
      (node (ref "CHIP_3") (pin "P21") (pinfunction "G6_P21") (pintype "bidirectional"))
      (node (ref "D83") (pin "1") (pinfunction "GREEN_CATHODE_1") (pintype "bidirectional"))
    )
    (net (code "128") (name "Net-(CHIP_3-G7)") (class "Default")
      (node (ref "CHIP_3") (pin "P27") (pinfunction "G7_P27") (pintype "bidirectional"))
      (node (ref "D92") (pin "1") (pinfunction "GREEN_CATHODE_1") (pintype "bidirectional"))
    )
    (net (code "129") (name "Net-(CHIP_3-G8)") (class "Default")
      (node (ref "CHIP_3") (pin "P51") (pinfunction "G8_P51") (pintype "bidirectional"))
      (node (ref "D85") (pin "1") (pinfunction "GREEN_CATHODE_1") (pintype "bidirectional"))
    )
    (net (code "130") (name "Net-(CHIP_3-G9)") (class "Default")
      (node (ref "CHIP_3") (pin "P45") (pinfunction "G9_P45") (pintype "bidirectional"))
      (node (ref "D86") (pin "1") (pinfunction "GREEN_CATHODE_1") (pintype "bidirectional"))
    )
    (net (code "131") (name "Net-(CHIP_3-G10)") (class "Default")
      (node (ref "CHIP_3") (pin "P36") (pinfunction "G10_P36") (pintype "bidirectional"))
      (node (ref "D82") (pin "1") (pinfunction "GREEN_CATHODE_1") (pintype "bidirectional"))
    )
    (net (code "132") (name "Net-(CHIP_3-G11)") (class "Default")
      (node (ref "CHIP_3") (pin "P30") (pinfunction "G11_P30") (pintype "bidirectional"))
      (node (ref "D84") (pin "1") (pinfunction "GREEN_CATHODE_1") (pintype "bidirectional"))
    )
    (net (code "133") (name "Net-(CHIP_3-G12)") (class "Default")
      (node (ref "CHIP_3") (pin "P48") (pinfunction "G12_P48") (pintype "bidirectional"))
      (node (ref "D94") (pin "1") (pinfunction "GREEN_CATHODE_1") (pintype "bidirectional"))
    )
    (net (code "134") (name "Net-(CHIP_3-G13)") (class "Default")
      (node (ref "CHIP_3") (pin "P42") (pinfunction "G13_P42") (pintype "bidirectional"))
      (node (ref "D93") (pin "1") (pinfunction "GREEN_CATHODE_1") (pintype "bidirectional"))
    )
    (net (code "135") (name "Net-(CHIP_3-G14)") (class "Default")
      (node (ref "CHIP_3") (pin "P39") (pinfunction "G14_P39") (pintype "bidirectional"))
      (node (ref "D81") (pin "1") (pinfunction "GREEN_CATHODE_1") (pintype "bidirectional"))
    )
    (net (code "136") (name "Net-(CHIP_3-G15)") (class "Default")
      (node (ref "CHIP_3") (pin "P33") (pinfunction "G15_P33") (pintype "bidirectional"))
      (node (ref "D89") (pin "1") (pinfunction "GREEN_CATHODE_1") (pintype "bidirectional"))
    )
    (net (code "137") (name "Net-(CHIP_3-R0)") (class "Default")
      (node (ref "CHIP_3") (pin "P8") (pinfunction "R0_P8") (pintype "bidirectional"))
      (node (ref "D90") (pin "3") (pinfunction "RED_CATHODE_3") (pintype "bidirectional"))
    )
    (net (code "138") (name "Net-(CHIP_3-R1)") (class "Default")
      (node (ref "CHIP_3") (pin "P14") (pinfunction "R1_P14") (pintype "bidirectional"))
      (node (ref "D91") (pin "3") (pinfunction "RED_CATHODE_3") (pintype "bidirectional"))
    )
    (net (code "139") (name "Net-(CHIP_3-R2)") (class "Default")
      (node (ref "CHIP_3") (pin "P17") (pinfunction "R2_P17") (pintype "bidirectional"))
      (node (ref "D87") (pin "3") (pinfunction "RED_CATHODE_3") (pintype "bidirectional"))
    )
    (net (code "140") (name "Net-(CHIP_3-R3)") (class "Default")
      (node (ref "CHIP_3") (pin "P23") (pinfunction "R3_P23") (pintype "bidirectional"))
      (node (ref "D95") (pin "3") (pinfunction "RED_CATHODE_3") (pintype "bidirectional"))
    )
    (net (code "141") (name "Net-(CHIP_3-R4)") (class "Default")
      (node (ref "CHIP_3") (pin "P5") (pinfunction "R4_P5") (pintype "bidirectional"))
      (node (ref "D96") (pin "3") (pinfunction "RED_CATHODE_3") (pintype "bidirectional"))
    )
    (net (code "142") (name "Net-(CHIP_3-R5)") (class "Default")
      (node (ref "CHIP_3") (pin "P11") (pinfunction "R5_P11") (pintype "bidirectional"))
      (node (ref "D88") (pin "3") (pinfunction "RED_CATHODE_3") (pintype "bidirectional"))
    )
    (net (code "143") (name "Net-(CHIP_3-R6)") (class "Default")
      (node (ref "CHIP_3") (pin "P20") (pinfunction "R6_P20") (pintype "bidirectional"))
      (node (ref "D83") (pin "3") (pinfunction "RED_CATHODE_3") (pintype "bidirectional"))
    )
    (net (code "144") (name "Net-(CHIP_3-R7)") (class "Default")
      (node (ref "CHIP_3") (pin "P26") (pinfunction "R7_P26") (pintype "bidirectional"))
      (node (ref "D92") (pin "3") (pinfunction "RED_CATHODE_3") (pintype "bidirectional"))
    )
    (net (code "145") (name "Net-(CHIP_3-R8)") (class "Default")
      (node (ref "CHIP_3") (pin "P52") (pinfunction "R8_P52") (pintype "bidirectional"))
      (node (ref "D85") (pin "3") (pinfunction "RED_CATHODE_3") (pintype "bidirectional"))
    )
    (net (code "146") (name "Net-(CHIP_3-R9)") (class "Default")
      (node (ref "CHIP_3") (pin "P46") (pinfunction "R9_P46") (pintype "bidirectional"))
      (node (ref "D86") (pin "3") (pinfunction "RED_CATHODE_3") (pintype "bidirectional"))
    )
    (net (code "147") (name "Net-(CHIP_3-R10)") (class "Default")
      (node (ref "CHIP_3") (pin "P37") (pinfunction "R10_P37") (pintype "bidirectional"))
      (node (ref "D82") (pin "3") (pinfunction "RED_CATHODE_3") (pintype "bidirectional"))
    )
    (net (code "148") (name "Net-(CHIP_3-R11)") (class "Default")
      (node (ref "CHIP_3") (pin "P31") (pinfunction "R11_P31") (pintype "bidirectional"))
      (node (ref "D84") (pin "3") (pinfunction "RED_CATHODE_3") (pintype "bidirectional"))
    )
    (net (code "149") (name "Net-(CHIP_3-R12)") (class "Default")
      (node (ref "CHIP_3") (pin "P49") (pinfunction "R12_P49") (pintype "bidirectional"))
      (node (ref "D94") (pin "3") (pinfunction "RED_CATHODE_3") (pintype "bidirectional"))
    )
    (net (code "150") (name "Net-(CHIP_3-R13)") (class "Default")
      (node (ref "CHIP_3") (pin "P43") (pinfunction "R13_P43") (pintype "bidirectional"))
      (node (ref "D93") (pin "3") (pinfunction "RED_CATHODE_3") (pintype "bidirectional"))
    )
    (net (code "151") (name "Net-(CHIP_3-R14)") (class "Default")
      (node (ref "CHIP_3") (pin "P40") (pinfunction "R14_P40") (pintype "bidirectional"))
      (node (ref "D81") (pin "3") (pinfunction "RED_CATHODE_3") (pintype "bidirectional"))
    )
    (net (code "152") (name "Net-(CHIP_3-R15)") (class "Default")
      (node (ref "CHIP_3") (pin "P34") (pinfunction "R15_P34") (pintype "bidirectional"))
      (node (ref "D89") (pin "3") (pinfunction "RED_CATHODE_3") (pintype "bidirectional"))
    )
    (net (code "153") (name "Net-(CHIP_3-SOUT)") (class "Default")
      (node (ref "CHIP_3") (pin "P28") (pinfunction "SOUT_P28") (pintype "bidirectional"))
      (node (ref "CHIP_4") (pin "P1") (pinfunction "SIN_P1") (pintype "bidirectional"))
      (node (ref "SOUT3") (pin "1") (pinfunction "1_1") (pintype "passive"))
    )
    (net (code "154") (name "Net-(CHIP_4-B0)") (class "Default")
      (node (ref "CHIP_4") (pin "P7") (pinfunction "B0_P7") (pintype "bidirectional"))
      (node (ref "D26") (pin "4") (pinfunction "BLUE_CATHODE_4") (pintype "bidirectional"))
    )
    (net (code "155") (name "Net-(CHIP_4-B1)") (class "Default")
      (node (ref "CHIP_4") (pin "P13") (pinfunction "B1_P13") (pintype "bidirectional"))
      (node (ref "D27") (pin "4") (pinfunction "BLUE_CATHODE_4") (pintype "bidirectional"))
    )
    (net (code "156") (name "Net-(CHIP_4-B2)") (class "Default")
      (node (ref "CHIP_4") (pin "P16") (pinfunction "B2_P16") (pintype "bidirectional"))
      (node (ref "D23") (pin "4") (pinfunction "BLUE_CATHODE_4") (pintype "bidirectional"))
    )
    (net (code "157") (name "Net-(CHIP_4-B3)") (class "Default")
      (node (ref "CHIP_4") (pin "P22") (pinfunction "B3_P22") (pintype "bidirectional"))
      (node (ref "D31") (pin "4") (pinfunction "BLUE_CATHODE_4") (pintype "bidirectional"))
    )
    (net (code "158") (name "Net-(CHIP_4-B4)") (class "Default")
      (node (ref "CHIP_4") (pin "P4") (pinfunction "B4_P4") (pintype "bidirectional"))
      (node (ref "D32") (pin "4") (pinfunction "BLUE_CATHODE_4") (pintype "bidirectional"))
    )
    (net (code "159") (name "Net-(CHIP_4-B5)") (class "Default")
      (node (ref "CHIP_4") (pin "P10") (pinfunction "B5_P10") (pintype "bidirectional"))
      (node (ref "D24") (pin "4") (pinfunction "BLUE_CATHODE_4") (pintype "bidirectional"))
    )
    (net (code "160") (name "Net-(CHIP_4-B6)") (class "Default")
      (node (ref "CHIP_4") (pin "P19") (pinfunction "B6_P19") (pintype "bidirectional"))
      (node (ref "D19") (pin "4") (pinfunction "BLUE_CATHODE_4") (pintype "bidirectional"))
    )
    (net (code "161") (name "Net-(CHIP_4-B7)") (class "Default")
      (node (ref "CHIP_4") (pin "P25") (pinfunction "B7_P25") (pintype "bidirectional"))
      (node (ref "D28") (pin "4") (pinfunction "BLUE_CATHODE_4") (pintype "bidirectional"))
    )
    (net (code "162") (name "Net-(CHIP_4-B8)") (class "Default")
      (node (ref "CHIP_4") (pin "P53") (pinfunction "B8_P53") (pintype "bidirectional"))
      (node (ref "D21") (pin "4") (pinfunction "BLUE_CATHODE_4") (pintype "bidirectional"))
    )
    (net (code "163") (name "Net-(CHIP_4-B9)") (class "Default")
      (node (ref "CHIP_4") (pin "P47") (pinfunction "B9_P47") (pintype "bidirectional"))
      (node (ref "D22") (pin "4") (pinfunction "BLUE_CATHODE_4") (pintype "bidirectional"))
    )
    (net (code "164") (name "Net-(CHIP_4-B10)") (class "Default")
      (node (ref "CHIP_4") (pin "P38") (pinfunction "B10_P38") (pintype "bidirectional"))
      (node (ref "D18") (pin "4") (pinfunction "BLUE_CATHODE_4") (pintype "bidirectional"))
    )
    (net (code "165") (name "Net-(CHIP_4-B11)") (class "Default")
      (node (ref "CHIP_4") (pin "P32") (pinfunction "B11_P32") (pintype "bidirectional"))
      (node (ref "D20") (pin "4") (pinfunction "BLUE_CATHODE_4") (pintype "bidirectional"))
    )
    (net (code "166") (name "Net-(CHIP_4-B12)") (class "Default")
      (node (ref "CHIP_4") (pin "P50") (pinfunction "B12_P50") (pintype "bidirectional"))
      (node (ref "D30") (pin "4") (pinfunction "BLUE_CATHODE_4") (pintype "bidirectional"))
    )
    (net (code "167") (name "Net-(CHIP_4-B13)") (class "Default")
      (node (ref "CHIP_4") (pin "P44") (pinfunction "B13_P44") (pintype "bidirectional"))
      (node (ref "D29") (pin "4") (pinfunction "BLUE_CATHODE_4") (pintype "bidirectional"))
    )
    (net (code "168") (name "Net-(CHIP_4-B14)") (class "Default")
      (node (ref "CHIP_4") (pin "P41") (pinfunction "B14_P41") (pintype "bidirectional"))
      (node (ref "D17") (pin "4") (pinfunction "BLUE_CATHODE_4") (pintype "bidirectional"))
    )
    (net (code "169") (name "Net-(CHIP_4-B15)") (class "Default")
      (node (ref "CHIP_4") (pin "P35") (pinfunction "B15_P35") (pintype "bidirectional"))
      (node (ref "D25") (pin "4") (pinfunction "BLUE_CATHODE_4") (pintype "bidirectional"))
    )
    (net (code "170") (name "Net-(CHIP_4-G0)") (class "Default")
      (node (ref "CHIP_4") (pin "P9") (pinfunction "G0_P9") (pintype "bidirectional"))
      (node (ref "D26") (pin "1") (pinfunction "GREEN_CATHODE_1") (pintype "bidirectional"))
    )
    (net (code "171") (name "Net-(CHIP_4-G1)") (class "Default")
      (node (ref "CHIP_4") (pin "P15") (pinfunction "G1_P15") (pintype "bidirectional"))
      (node (ref "D27") (pin "1") (pinfunction "GREEN_CATHODE_1") (pintype "bidirectional"))
    )
    (net (code "172") (name "Net-(CHIP_4-G2)") (class "Default")
      (node (ref "CHIP_4") (pin "P18") (pinfunction "G2_P18") (pintype "bidirectional"))
      (node (ref "D23") (pin "1") (pinfunction "GREEN_CATHODE_1") (pintype "bidirectional"))
    )
    (net (code "173") (name "Net-(CHIP_4-G3)") (class "Default")
      (node (ref "CHIP_4") (pin "P24") (pinfunction "G3_P24") (pintype "bidirectional"))
      (node (ref "D31") (pin "1") (pinfunction "GREEN_CATHODE_1") (pintype "bidirectional"))
    )
    (net (code "174") (name "Net-(CHIP_4-G4)") (class "Default")
      (node (ref "CHIP_4") (pin "P6") (pinfunction "G4_P6") (pintype "bidirectional"))
      (node (ref "D32") (pin "1") (pinfunction "GREEN_CATHODE_1") (pintype "bidirectional"))
    )
    (net (code "175") (name "Net-(CHIP_4-G5)") (class "Default")
      (node (ref "CHIP_4") (pin "P12") (pinfunction "G5_P12") (pintype "bidirectional"))
      (node (ref "D24") (pin "1") (pinfunction "GREEN_CATHODE_1") (pintype "bidirectional"))
    )
    (net (code "176") (name "Net-(CHIP_4-G6)") (class "Default")
      (node (ref "CHIP_4") (pin "P21") (pinfunction "G6_P21") (pintype "bidirectional"))
      (node (ref "D19") (pin "1") (pinfunction "GREEN_CATHODE_1") (pintype "bidirectional"))
    )
    (net (code "177") (name "Net-(CHIP_4-G7)") (class "Default")
      (node (ref "CHIP_4") (pin "P27") (pinfunction "G7_P27") (pintype "bidirectional"))
      (node (ref "D28") (pin "1") (pinfunction "GREEN_CATHODE_1") (pintype "bidirectional"))
    )
    (net (code "178") (name "Net-(CHIP_4-G8)") (class "Default")
      (node (ref "CHIP_4") (pin "P51") (pinfunction "G8_P51") (pintype "bidirectional"))
      (node (ref "D21") (pin "1") (pinfunction "GREEN_CATHODE_1") (pintype "bidirectional"))
    )
    (net (code "179") (name "Net-(CHIP_4-G9)") (class "Default")
      (node (ref "CHIP_4") (pin "P45") (pinfunction "G9_P45") (pintype "bidirectional"))
      (node (ref "D22") (pin "1") (pinfunction "GREEN_CATHODE_1") (pintype "bidirectional"))
    )
    (net (code "180") (name "Net-(CHIP_4-G10)") (class "Default")
      (node (ref "CHIP_4") (pin "P36") (pinfunction "G10_P36") (pintype "bidirectional"))
      (node (ref "D18") (pin "1") (pinfunction "GREEN_CATHODE_1") (pintype "bidirectional"))
    )
    (net (code "181") (name "Net-(CHIP_4-G11)") (class "Default")
      (node (ref "CHIP_4") (pin "P30") (pinfunction "G11_P30") (pintype "bidirectional"))
      (node (ref "D20") (pin "1") (pinfunction "GREEN_CATHODE_1") (pintype "bidirectional"))
    )
    (net (code "182") (name "Net-(CHIP_4-G12)") (class "Default")
      (node (ref "CHIP_4") (pin "P48") (pinfunction "G12_P48") (pintype "bidirectional"))
      (node (ref "D30") (pin "1") (pinfunction "GREEN_CATHODE_1") (pintype "bidirectional"))
    )
    (net (code "183") (name "Net-(CHIP_4-G13)") (class "Default")
      (node (ref "CHIP_4") (pin "P42") (pinfunction "G13_P42") (pintype "bidirectional"))
      (node (ref "D29") (pin "1") (pinfunction "GREEN_CATHODE_1") (pintype "bidirectional"))
    )
    (net (code "184") (name "Net-(CHIP_4-G14)") (class "Default")
      (node (ref "CHIP_4") (pin "P39") (pinfunction "G14_P39") (pintype "bidirectional"))
      (node (ref "D17") (pin "1") (pinfunction "GREEN_CATHODE_1") (pintype "bidirectional"))
    )
    (net (code "185") (name "Net-(CHIP_4-G15)") (class "Default")
      (node (ref "CHIP_4") (pin "P33") (pinfunction "G15_P33") (pintype "bidirectional"))
      (node (ref "D25") (pin "1") (pinfunction "GREEN_CATHODE_1") (pintype "bidirectional"))
    )
    (net (code "186") (name "Net-(CHIP_4-R0)") (class "Default")
      (node (ref "CHIP_4") (pin "P8") (pinfunction "R0_P8") (pintype "bidirectional"))
      (node (ref "D26") (pin "3") (pinfunction "RED_CATHODE_3") (pintype "bidirectional"))
    )
    (net (code "187") (name "Net-(CHIP_4-R1)") (class "Default")
      (node (ref "CHIP_4") (pin "P14") (pinfunction "R1_P14") (pintype "bidirectional"))
      (node (ref "D27") (pin "3") (pinfunction "RED_CATHODE_3") (pintype "bidirectional"))
    )
    (net (code "188") (name "Net-(CHIP_4-R2)") (class "Default")
      (node (ref "CHIP_4") (pin "P17") (pinfunction "R2_P17") (pintype "bidirectional"))
      (node (ref "D23") (pin "3") (pinfunction "RED_CATHODE_3") (pintype "bidirectional"))
    )
    (net (code "189") (name "Net-(CHIP_4-R3)") (class "Default")
      (node (ref "CHIP_4") (pin "P23") (pinfunction "R3_P23") (pintype "bidirectional"))
      (node (ref "D31") (pin "3") (pinfunction "RED_CATHODE_3") (pintype "bidirectional"))
    )
    (net (code "190") (name "Net-(CHIP_4-R4)") (class "Default")
      (node (ref "CHIP_4") (pin "P5") (pinfunction "R4_P5") (pintype "bidirectional"))
      (node (ref "D32") (pin "3") (pinfunction "RED_CATHODE_3") (pintype "bidirectional"))
    )
    (net (code "191") (name "Net-(CHIP_4-R5)") (class "Default")
      (node (ref "CHIP_4") (pin "P11") (pinfunction "R5_P11") (pintype "bidirectional"))
      (node (ref "D24") (pin "3") (pinfunction "RED_CATHODE_3") (pintype "bidirectional"))
    )
    (net (code "192") (name "Net-(CHIP_4-R6)") (class "Default")
      (node (ref "CHIP_4") (pin "P20") (pinfunction "R6_P20") (pintype "bidirectional"))
      (node (ref "D19") (pin "3") (pinfunction "RED_CATHODE_3") (pintype "bidirectional"))
    )
    (net (code "193") (name "Net-(CHIP_4-R7)") (class "Default")
      (node (ref "CHIP_4") (pin "P26") (pinfunction "R7_P26") (pintype "bidirectional"))
      (node (ref "D28") (pin "3") (pinfunction "RED_CATHODE_3") (pintype "bidirectional"))
    )
    (net (code "194") (name "Net-(CHIP_4-R8)") (class "Default")
      (node (ref "CHIP_4") (pin "P52") (pinfunction "R8_P52") (pintype "bidirectional"))
      (node (ref "D21") (pin "3") (pinfunction "RED_CATHODE_3") (pintype "bidirectional"))
    )
    (net (code "195") (name "Net-(CHIP_4-R9)") (class "Default")
      (node (ref "CHIP_4") (pin "P46") (pinfunction "R9_P46") (pintype "bidirectional"))
      (node (ref "D22") (pin "3") (pinfunction "RED_CATHODE_3") (pintype "bidirectional"))
    )
    (net (code "196") (name "Net-(CHIP_4-R10)") (class "Default")
      (node (ref "CHIP_4") (pin "P37") (pinfunction "R10_P37") (pintype "bidirectional"))
      (node (ref "D18") (pin "3") (pinfunction "RED_CATHODE_3") (pintype "bidirectional"))
    )
    (net (code "197") (name "Net-(CHIP_4-R11)") (class "Default")
      (node (ref "CHIP_4") (pin "P31") (pinfunction "R11_P31") (pintype "bidirectional"))
      (node (ref "D20") (pin "3") (pinfunction "RED_CATHODE_3") (pintype "bidirectional"))
    )
    (net (code "198") (name "Net-(CHIP_4-R12)") (class "Default")
      (node (ref "CHIP_4") (pin "P49") (pinfunction "R12_P49") (pintype "bidirectional"))
      (node (ref "D30") (pin "3") (pinfunction "RED_CATHODE_3") (pintype "bidirectional"))
    )
    (net (code "199") (name "Net-(CHIP_4-R13)") (class "Default")
      (node (ref "CHIP_4") (pin "P43") (pinfunction "R13_P43") (pintype "bidirectional"))
      (node (ref "D29") (pin "3") (pinfunction "RED_CATHODE_3") (pintype "bidirectional"))
    )
    (net (code "200") (name "Net-(CHIP_4-R14)") (class "Default")
      (node (ref "CHIP_4") (pin "P40") (pinfunction "R14_P40") (pintype "bidirectional"))
      (node (ref "D17") (pin "3") (pinfunction "RED_CATHODE_3") (pintype "bidirectional"))
    )
    (net (code "201") (name "Net-(CHIP_4-R15)") (class "Default")
      (node (ref "CHIP_4") (pin "P34") (pinfunction "R15_P34") (pintype "bidirectional"))
      (node (ref "D25") (pin "3") (pinfunction "RED_CATHODE_3") (pintype "bidirectional"))
    )
    (net (code "202") (name "Net-(CHIP_4-SOUT)") (class "Default")
      (node (ref "CHIP_4") (pin "P28") (pinfunction "SOUT_P28") (pintype "bidirectional"))
      (node (ref "CHIP_5") (pin "P1") (pinfunction "SIN_P1") (pintype "bidirectional"))
      (node (ref "SOUT4") (pin "1") (pinfunction "1_1") (pintype "passive"))
    )
    (net (code "203") (name "Net-(CHIP_5-B0)") (class "Default")
      (node (ref "CHIP_5") (pin "P7") (pinfunction "B0_P7") (pintype "bidirectional"))
      (node (ref "D42") (pin "4") (pinfunction "BLUE_CATHODE_4") (pintype "bidirectional"))
    )
    (net (code "204") (name "Net-(CHIP_5-B1)") (class "Default")
      (node (ref "CHIP_5") (pin "P13") (pinfunction "B1_P13") (pintype "bidirectional"))
      (node (ref "D43") (pin "4") (pinfunction "BLUE_CATHODE_4") (pintype "bidirectional"))
    )
    (net (code "205") (name "Net-(CHIP_5-B2)") (class "Default")
      (node (ref "CHIP_5") (pin "P16") (pinfunction "B2_P16") (pintype "bidirectional"))
      (node (ref "D39") (pin "4") (pinfunction "BLUE_CATHODE_4") (pintype "bidirectional"))
    )
    (net (code "206") (name "Net-(CHIP_5-B3)") (class "Default")
      (node (ref "CHIP_5") (pin "P22") (pinfunction "B3_P22") (pintype "bidirectional"))
      (node (ref "D47") (pin "4") (pinfunction "BLUE_CATHODE_4") (pintype "bidirectional"))
    )
    (net (code "207") (name "Net-(CHIP_5-B4)") (class "Default")
      (node (ref "CHIP_5") (pin "P4") (pinfunction "B4_P4") (pintype "bidirectional"))
      (node (ref "D48") (pin "4") (pinfunction "BLUE_CATHODE_4") (pintype "bidirectional"))
    )
    (net (code "208") (name "Net-(CHIP_5-B5)") (class "Default")
      (node (ref "CHIP_5") (pin "P10") (pinfunction "B5_P10") (pintype "bidirectional"))
      (node (ref "D40") (pin "4") (pinfunction "BLUE_CATHODE_4") (pintype "bidirectional"))
    )
    (net (code "209") (name "Net-(CHIP_5-B6)") (class "Default")
      (node (ref "CHIP_5") (pin "P19") (pinfunction "B6_P19") (pintype "bidirectional"))
      (node (ref "D35") (pin "4") (pinfunction "BLUE_CATHODE_4") (pintype "bidirectional"))
    )
    (net (code "210") (name "Net-(CHIP_5-B7)") (class "Default")
      (node (ref "CHIP_5") (pin "P25") (pinfunction "B7_P25") (pintype "bidirectional"))
      (node (ref "D44") (pin "4") (pinfunction "BLUE_CATHODE_4") (pintype "bidirectional"))
    )
    (net (code "211") (name "Net-(CHIP_5-B8)") (class "Default")
      (node (ref "CHIP_5") (pin "P53") (pinfunction "B8_P53") (pintype "bidirectional"))
      (node (ref "D37") (pin "4") (pinfunction "BLUE_CATHODE_4") (pintype "bidirectional"))
    )
    (net (code "212") (name "Net-(CHIP_5-B9)") (class "Default")
      (node (ref "CHIP_5") (pin "P47") (pinfunction "B9_P47") (pintype "bidirectional"))
      (node (ref "D38") (pin "4") (pinfunction "BLUE_CATHODE_4") (pintype "bidirectional"))
    )
    (net (code "213") (name "Net-(CHIP_5-B10)") (class "Default")
      (node (ref "CHIP_5") (pin "P38") (pinfunction "B10_P38") (pintype "bidirectional"))
      (node (ref "D34") (pin "4") (pinfunction "BLUE_CATHODE_4") (pintype "bidirectional"))
    )
    (net (code "214") (name "Net-(CHIP_5-B11)") (class "Default")
      (node (ref "CHIP_5") (pin "P32") (pinfunction "B11_P32") (pintype "bidirectional"))
      (node (ref "D36") (pin "4") (pinfunction "BLUE_CATHODE_4") (pintype "bidirectional"))
    )
    (net (code "215") (name "Net-(CHIP_5-B12)") (class "Default")
      (node (ref "CHIP_5") (pin "P50") (pinfunction "B12_P50") (pintype "bidirectional"))
      (node (ref "D46") (pin "4") (pinfunction "BLUE_CATHODE_4") (pintype "bidirectional"))
    )
    (net (code "216") (name "Net-(CHIP_5-B13)") (class "Default")
      (node (ref "CHIP_5") (pin "P44") (pinfunction "B13_P44") (pintype "bidirectional"))
      (node (ref "D45") (pin "4") (pinfunction "BLUE_CATHODE_4") (pintype "bidirectional"))
    )
    (net (code "217") (name "Net-(CHIP_5-B14)") (class "Default")
      (node (ref "CHIP_5") (pin "P41") (pinfunction "B14_P41") (pintype "bidirectional"))
      (node (ref "D33") (pin "4") (pinfunction "BLUE_CATHODE_4") (pintype "bidirectional"))
    )
    (net (code "218") (name "Net-(CHIP_5-B15)") (class "Default")
      (node (ref "CHIP_5") (pin "P35") (pinfunction "B15_P35") (pintype "bidirectional"))
      (node (ref "D41") (pin "4") (pinfunction "BLUE_CATHODE_4") (pintype "bidirectional"))
    )
    (net (code "219") (name "Net-(CHIP_5-G0)") (class "Default")
      (node (ref "CHIP_5") (pin "P9") (pinfunction "G0_P9") (pintype "bidirectional"))
      (node (ref "D42") (pin "1") (pinfunction "GREEN_CATHODE_1") (pintype "bidirectional"))
    )
    (net (code "220") (name "Net-(CHIP_5-G1)") (class "Default")
      (node (ref "CHIP_5") (pin "P15") (pinfunction "G1_P15") (pintype "bidirectional"))
      (node (ref "D43") (pin "1") (pinfunction "GREEN_CATHODE_1") (pintype "bidirectional"))
    )
    (net (code "221") (name "Net-(CHIP_5-G2)") (class "Default")
      (node (ref "CHIP_5") (pin "P18") (pinfunction "G2_P18") (pintype "bidirectional"))
      (node (ref "D39") (pin "1") (pinfunction "GREEN_CATHODE_1") (pintype "bidirectional"))
    )
    (net (code "222") (name "Net-(CHIP_5-G3)") (class "Default")
      (node (ref "CHIP_5") (pin "P24") (pinfunction "G3_P24") (pintype "bidirectional"))
      (node (ref "D47") (pin "1") (pinfunction "GREEN_CATHODE_1") (pintype "bidirectional"))
    )
    (net (code "223") (name "Net-(CHIP_5-G4)") (class "Default")
      (node (ref "CHIP_5") (pin "P6") (pinfunction "G4_P6") (pintype "bidirectional"))
      (node (ref "D48") (pin "1") (pinfunction "GREEN_CATHODE_1") (pintype "bidirectional"))
    )
    (net (code "224") (name "Net-(CHIP_5-G5)") (class "Default")
      (node (ref "CHIP_5") (pin "P12") (pinfunction "G5_P12") (pintype "bidirectional"))
      (node (ref "D40") (pin "1") (pinfunction "GREEN_CATHODE_1") (pintype "bidirectional"))
    )
    (net (code "225") (name "Net-(CHIP_5-G6)") (class "Default")
      (node (ref "CHIP_5") (pin "P21") (pinfunction "G6_P21") (pintype "bidirectional"))
      (node (ref "D35") (pin "1") (pinfunction "GREEN_CATHODE_1") (pintype "bidirectional"))
    )
    (net (code "226") (name "Net-(CHIP_5-G7)") (class "Default")
      (node (ref "CHIP_5") (pin "P27") (pinfunction "G7_P27") (pintype "bidirectional"))
      (node (ref "D44") (pin "1") (pinfunction "GREEN_CATHODE_1") (pintype "bidirectional"))
    )
    (net (code "227") (name "Net-(CHIP_5-G8)") (class "Default")
      (node (ref "CHIP_5") (pin "P51") (pinfunction "G8_P51") (pintype "bidirectional"))
      (node (ref "D37") (pin "1") (pinfunction "GREEN_CATHODE_1") (pintype "bidirectional"))
    )
    (net (code "228") (name "Net-(CHIP_5-G9)") (class "Default")
      (node (ref "CHIP_5") (pin "P45") (pinfunction "G9_P45") (pintype "bidirectional"))
      (node (ref "D38") (pin "1") (pinfunction "GREEN_CATHODE_1") (pintype "bidirectional"))
    )
    (net (code "229") (name "Net-(CHIP_5-G10)") (class "Default")
      (node (ref "CHIP_5") (pin "P36") (pinfunction "G10_P36") (pintype "bidirectional"))
      (node (ref "D34") (pin "1") (pinfunction "GREEN_CATHODE_1") (pintype "bidirectional"))
    )
    (net (code "230") (name "Net-(CHIP_5-G11)") (class "Default")
      (node (ref "CHIP_5") (pin "P30") (pinfunction "G11_P30") (pintype "bidirectional"))
      (node (ref "D36") (pin "1") (pinfunction "GREEN_CATHODE_1") (pintype "bidirectional"))
    )
    (net (code "231") (name "Net-(CHIP_5-G12)") (class "Default")
      (node (ref "CHIP_5") (pin "P48") (pinfunction "G12_P48") (pintype "bidirectional"))
      (node (ref "D46") (pin "1") (pinfunction "GREEN_CATHODE_1") (pintype "bidirectional"))
    )
    (net (code "232") (name "Net-(CHIP_5-G13)") (class "Default")
      (node (ref "CHIP_5") (pin "P42") (pinfunction "G13_P42") (pintype "bidirectional"))
      (node (ref "D45") (pin "1") (pinfunction "GREEN_CATHODE_1") (pintype "bidirectional"))
    )
    (net (code "233") (name "Net-(CHIP_5-G14)") (class "Default")
      (node (ref "CHIP_5") (pin "P39") (pinfunction "G14_P39") (pintype "bidirectional"))
      (node (ref "D33") (pin "1") (pinfunction "GREEN_CATHODE_1") (pintype "bidirectional"))
    )
    (net (code "234") (name "Net-(CHIP_5-G15)") (class "Default")
      (node (ref "CHIP_5") (pin "P33") (pinfunction "G15_P33") (pintype "bidirectional"))
      (node (ref "D41") (pin "1") (pinfunction "GREEN_CATHODE_1") (pintype "bidirectional"))
    )
    (net (code "235") (name "Net-(CHIP_5-R0)") (class "Default")
      (node (ref "CHIP_5") (pin "P8") (pinfunction "R0_P8") (pintype "bidirectional"))
      (node (ref "D42") (pin "3") (pinfunction "RED_CATHODE_3") (pintype "bidirectional"))
    )
    (net (code "236") (name "Net-(CHIP_5-R1)") (class "Default")
      (node (ref "CHIP_5") (pin "P14") (pinfunction "R1_P14") (pintype "bidirectional"))
      (node (ref "D43") (pin "3") (pinfunction "RED_CATHODE_3") (pintype "bidirectional"))
    )
    (net (code "237") (name "Net-(CHIP_5-R2)") (class "Default")
      (node (ref "CHIP_5") (pin "P17") (pinfunction "R2_P17") (pintype "bidirectional"))
      (node (ref "D39") (pin "3") (pinfunction "RED_CATHODE_3") (pintype "bidirectional"))
    )
    (net (code "238") (name "Net-(CHIP_5-R3)") (class "Default")
      (node (ref "CHIP_5") (pin "P23") (pinfunction "R3_P23") (pintype "bidirectional"))
      (node (ref "D47") (pin "3") (pinfunction "RED_CATHODE_3") (pintype "bidirectional"))
    )
    (net (code "239") (name "Net-(CHIP_5-R4)") (class "Default")
      (node (ref "CHIP_5") (pin "P5") (pinfunction "R4_P5") (pintype "bidirectional"))
      (node (ref "D48") (pin "3") (pinfunction "RED_CATHODE_3") (pintype "bidirectional"))
    )
    (net (code "240") (name "Net-(CHIP_5-R5)") (class "Default")
      (node (ref "CHIP_5") (pin "P11") (pinfunction "R5_P11") (pintype "bidirectional"))
      (node (ref "D40") (pin "3") (pinfunction "RED_CATHODE_3") (pintype "bidirectional"))
    )
    (net (code "241") (name "Net-(CHIP_5-R6)") (class "Default")
      (node (ref "CHIP_5") (pin "P20") (pinfunction "R6_P20") (pintype "bidirectional"))
      (node (ref "D35") (pin "3") (pinfunction "RED_CATHODE_3") (pintype "bidirectional"))
    )
    (net (code "242") (name "Net-(CHIP_5-R7)") (class "Default")
      (node (ref "CHIP_5") (pin "P26") (pinfunction "R7_P26") (pintype "bidirectional"))
      (node (ref "D44") (pin "3") (pinfunction "RED_CATHODE_3") (pintype "bidirectional"))
    )
    (net (code "243") (name "Net-(CHIP_5-R8)") (class "Default")
      (node (ref "CHIP_5") (pin "P52") (pinfunction "R8_P52") (pintype "bidirectional"))
      (node (ref "D37") (pin "3") (pinfunction "RED_CATHODE_3") (pintype "bidirectional"))
    )
    (net (code "244") (name "Net-(CHIP_5-R9)") (class "Default")
      (node (ref "CHIP_5") (pin "P46") (pinfunction "R9_P46") (pintype "bidirectional"))
      (node (ref "D38") (pin "3") (pinfunction "RED_CATHODE_3") (pintype "bidirectional"))
    )
    (net (code "245") (name "Net-(CHIP_5-R10)") (class "Default")
      (node (ref "CHIP_5") (pin "P37") (pinfunction "R10_P37") (pintype "bidirectional"))
      (node (ref "D34") (pin "3") (pinfunction "RED_CATHODE_3") (pintype "bidirectional"))
    )
    (net (code "246") (name "Net-(CHIP_5-R11)") (class "Default")
      (node (ref "CHIP_5") (pin "P31") (pinfunction "R11_P31") (pintype "bidirectional"))
      (node (ref "D36") (pin "3") (pinfunction "RED_CATHODE_3") (pintype "bidirectional"))
    )
    (net (code "247") (name "Net-(CHIP_5-R12)") (class "Default")
      (node (ref "CHIP_5") (pin "P49") (pinfunction "R12_P49") (pintype "bidirectional"))
      (node (ref "D46") (pin "3") (pinfunction "RED_CATHODE_3") (pintype "bidirectional"))
    )
    (net (code "248") (name "Net-(CHIP_5-R13)") (class "Default")
      (node (ref "CHIP_5") (pin "P43") (pinfunction "R13_P43") (pintype "bidirectional"))
      (node (ref "D45") (pin "3") (pinfunction "RED_CATHODE_3") (pintype "bidirectional"))
    )
    (net (code "249") (name "Net-(CHIP_5-R14)") (class "Default")
      (node (ref "CHIP_5") (pin "P40") (pinfunction "R14_P40") (pintype "bidirectional"))
      (node (ref "D33") (pin "3") (pinfunction "RED_CATHODE_3") (pintype "bidirectional"))
    )
    (net (code "250") (name "Net-(CHIP_5-R15)") (class "Default")
      (node (ref "CHIP_5") (pin "P34") (pinfunction "R15_P34") (pintype "bidirectional"))
      (node (ref "D41") (pin "3") (pinfunction "RED_CATHODE_3") (pintype "bidirectional"))
    )
    (net (code "251") (name "Net-(CHIP_5-SOUT)") (class "Default")
      (node (ref "CHIP_5") (pin "P28") (pinfunction "SOUT_P28") (pintype "bidirectional"))
      (node (ref "CHIP_6") (pin "P1") (pinfunction "SIN_P1") (pintype "bidirectional"))
      (node (ref "SOUT5") (pin "1") (pinfunction "1_1") (pintype "passive"))
    )
    (net (code "252") (name "Net-(CHIP_6-B0)") (class "Default")
      (node (ref "CHIP_6") (pin "P7") (pinfunction "B0_P7") (pintype "bidirectional"))
      (node (ref "D10") (pin "4") (pinfunction "BLUE_CATHODE_4") (pintype "bidirectional"))
    )
    (net (code "253") (name "Net-(CHIP_6-B1)") (class "Default")
      (node (ref "CHIP_6") (pin "P13") (pinfunction "B1_P13") (pintype "bidirectional"))
      (node (ref "D11") (pin "4") (pinfunction "BLUE_CATHODE_4") (pintype "bidirectional"))
    )
    (net (code "254") (name "Net-(CHIP_6-B2)") (class "Default")
      (node (ref "CHIP_6") (pin "P16") (pinfunction "B2_P16") (pintype "bidirectional"))
      (node (ref "D7") (pin "4") (pinfunction "BLUE_CATHODE_4") (pintype "bidirectional"))
    )
    (net (code "255") (name "Net-(CHIP_6-B3)") (class "Default")
      (node (ref "CHIP_6") (pin "P22") (pinfunction "B3_P22") (pintype "bidirectional"))
      (node (ref "D15") (pin "4") (pinfunction "BLUE_CATHODE_4") (pintype "bidirectional"))
    )
    (net (code "256") (name "Net-(CHIP_6-B4)") (class "Default")
      (node (ref "CHIP_6") (pin "P4") (pinfunction "B4_P4") (pintype "bidirectional"))
      (node (ref "D16") (pin "4") (pinfunction "BLUE_CATHODE_4") (pintype "bidirectional"))
    )
    (net (code "257") (name "Net-(CHIP_6-B5)") (class "Default")
      (node (ref "CHIP_6") (pin "P10") (pinfunction "B5_P10") (pintype "bidirectional"))
      (node (ref "D8") (pin "4") (pinfunction "BLUE_CATHODE_4") (pintype "bidirectional"))
    )
    (net (code "258") (name "Net-(CHIP_6-B6)") (class "Default")
      (node (ref "CHIP_6") (pin "P19") (pinfunction "B6_P19") (pintype "bidirectional"))
      (node (ref "D3") (pin "4") (pinfunction "BLUE_CATHODE_4") (pintype "bidirectional"))
    )
    (net (code "259") (name "Net-(CHIP_6-B7)") (class "Default")
      (node (ref "CHIP_6") (pin "P25") (pinfunction "B7_P25") (pintype "bidirectional"))
      (node (ref "D12") (pin "4") (pinfunction "BLUE_CATHODE_4") (pintype "bidirectional"))
    )
    (net (code "260") (name "Net-(CHIP_6-B8)") (class "Default")
      (node (ref "CHIP_6") (pin "P53") (pinfunction "B8_P53") (pintype "bidirectional"))
      (node (ref "D5") (pin "4") (pinfunction "BLUE_CATHODE_4") (pintype "bidirectional"))
    )
    (net (code "261") (name "Net-(CHIP_6-B9)") (class "Default")
      (node (ref "CHIP_6") (pin "P47") (pinfunction "B9_P47") (pintype "bidirectional"))
      (node (ref "D6") (pin "4") (pinfunction "BLUE_CATHODE_4") (pintype "bidirectional"))
    )
    (net (code "262") (name "Net-(CHIP_6-B10)") (class "Default")
      (node (ref "CHIP_6") (pin "P38") (pinfunction "B10_P38") (pintype "bidirectional"))
      (node (ref "D2") (pin "4") (pinfunction "BLUE_CATHODE_4") (pintype "bidirectional"))
    )
    (net (code "263") (name "Net-(CHIP_6-B11)") (class "Default")
      (node (ref "CHIP_6") (pin "P32") (pinfunction "B11_P32") (pintype "bidirectional"))
      (node (ref "D4") (pin "4") (pinfunction "BLUE_CATHODE_4") (pintype "bidirectional"))
    )
    (net (code "264") (name "Net-(CHIP_6-B12)") (class "Default")
      (node (ref "CHIP_6") (pin "P50") (pinfunction "B12_P50") (pintype "bidirectional"))
      (node (ref "D14") (pin "4") (pinfunction "BLUE_CATHODE_4") (pintype "bidirectional"))
    )
    (net (code "265") (name "Net-(CHIP_6-B13)") (class "Default")
      (node (ref "CHIP_6") (pin "P44") (pinfunction "B13_P44") (pintype "bidirectional"))
      (node (ref "D13") (pin "4") (pinfunction "BLUE_CATHODE_4") (pintype "bidirectional"))
    )
    (net (code "266") (name "Net-(CHIP_6-B14)") (class "Default")
      (node (ref "CHIP_6") (pin "P41") (pinfunction "B14_P41") (pintype "bidirectional"))
      (node (ref "D1") (pin "4") (pinfunction "BLUE_CATHODE_4") (pintype "bidirectional"))
    )
    (net (code "267") (name "Net-(CHIP_6-B15)") (class "Default")
      (node (ref "CHIP_6") (pin "P35") (pinfunction "B15_P35") (pintype "bidirectional"))
      (node (ref "D9") (pin "4") (pinfunction "BLUE_CATHODE_4") (pintype "bidirectional"))
    )
    (net (code "268") (name "Net-(CHIP_6-G0)") (class "Default")
      (node (ref "CHIP_6") (pin "P9") (pinfunction "G0_P9") (pintype "bidirectional"))
      (node (ref "D10") (pin "1") (pinfunction "GREEN_CATHODE_1") (pintype "bidirectional"))
    )
    (net (code "269") (name "Net-(CHIP_6-G1)") (class "Default")
      (node (ref "CHIP_6") (pin "P15") (pinfunction "G1_P15") (pintype "bidirectional"))
      (node (ref "D11") (pin "1") (pinfunction "GREEN_CATHODE_1") (pintype "bidirectional"))
    )
    (net (code "270") (name "Net-(CHIP_6-G2)") (class "Default")
      (node (ref "CHIP_6") (pin "P18") (pinfunction "G2_P18") (pintype "bidirectional"))
      (node (ref "D7") (pin "1") (pinfunction "GREEN_CATHODE_1") (pintype "bidirectional"))
    )
    (net (code "271") (name "Net-(CHIP_6-G3)") (class "Default")
      (node (ref "CHIP_6") (pin "P24") (pinfunction "G3_P24") (pintype "bidirectional"))
      (node (ref "D15") (pin "1") (pinfunction "GREEN_CATHODE_1") (pintype "bidirectional"))
    )
    (net (code "272") (name "Net-(CHIP_6-G4)") (class "Default")
      (node (ref "CHIP_6") (pin "P6") (pinfunction "G4_P6") (pintype "bidirectional"))
      (node (ref "D16") (pin "1") (pinfunction "GREEN_CATHODE_1") (pintype "bidirectional"))
    )
    (net (code "273") (name "Net-(CHIP_6-G5)") (class "Default")
      (node (ref "CHIP_6") (pin "P12") (pinfunction "G5_P12") (pintype "bidirectional"))
      (node (ref "D8") (pin "1") (pinfunction "GREEN_CATHODE_1") (pintype "bidirectional"))
    )
    (net (code "274") (name "Net-(CHIP_6-G6)") (class "Default")
      (node (ref "CHIP_6") (pin "P21") (pinfunction "G6_P21") (pintype "bidirectional"))
      (node (ref "D3") (pin "1") (pinfunction "GREEN_CATHODE_1") (pintype "bidirectional"))
    )
    (net (code "275") (name "Net-(CHIP_6-G7)") (class "Default")
      (node (ref "CHIP_6") (pin "P27") (pinfunction "G7_P27") (pintype "bidirectional"))
      (node (ref "D12") (pin "1") (pinfunction "GREEN_CATHODE_1") (pintype "bidirectional"))
    )
    (net (code "276") (name "Net-(CHIP_6-G8)") (class "Default")
      (node (ref "CHIP_6") (pin "P51") (pinfunction "G8_P51") (pintype "bidirectional"))
      (node (ref "D5") (pin "1") (pinfunction "GREEN_CATHODE_1") (pintype "bidirectional"))
    )
    (net (code "277") (name "Net-(CHIP_6-G9)") (class "Default")
      (node (ref "CHIP_6") (pin "P45") (pinfunction "G9_P45") (pintype "bidirectional"))
      (node (ref "D6") (pin "1") (pinfunction "GREEN_CATHODE_1") (pintype "bidirectional"))
    )
    (net (code "278") (name "Net-(CHIP_6-G10)") (class "Default")
      (node (ref "CHIP_6") (pin "P36") (pinfunction "G10_P36") (pintype "bidirectional"))
      (node (ref "D2") (pin "1") (pinfunction "GREEN_CATHODE_1") (pintype "bidirectional"))
    )
    (net (code "279") (name "Net-(CHIP_6-G11)") (class "Default")
      (node (ref "CHIP_6") (pin "P30") (pinfunction "G11_P30") (pintype "bidirectional"))
      (node (ref "D4") (pin "1") (pinfunction "GREEN_CATHODE_1") (pintype "bidirectional"))
    )
    (net (code "280") (name "Net-(CHIP_6-G12)") (class "Default")
      (node (ref "CHIP_6") (pin "P48") (pinfunction "G12_P48") (pintype "bidirectional"))
      (node (ref "D14") (pin "1") (pinfunction "GREEN_CATHODE_1") (pintype "bidirectional"))
    )
    (net (code "281") (name "Net-(CHIP_6-G13)") (class "Default")
      (node (ref "CHIP_6") (pin "P42") (pinfunction "G13_P42") (pintype "bidirectional"))
      (node (ref "D13") (pin "1") (pinfunction "GREEN_CATHODE_1") (pintype "bidirectional"))
    )
    (net (code "282") (name "Net-(CHIP_6-G14)") (class "Default")
      (node (ref "CHIP_6") (pin "P39") (pinfunction "G14_P39") (pintype "bidirectional"))
      (node (ref "D1") (pin "1") (pinfunction "GREEN_CATHODE_1") (pintype "bidirectional"))
    )
    (net (code "283") (name "Net-(CHIP_6-G15)") (class "Default")
      (node (ref "CHIP_6") (pin "P33") (pinfunction "G15_P33") (pintype "bidirectional"))
      (node (ref "D9") (pin "1") (pinfunction "GREEN_CATHODE_1") (pintype "bidirectional"))
    )
    (net (code "284") (name "Net-(CHIP_6-R0)") (class "Default")
      (node (ref "CHIP_6") (pin "P8") (pinfunction "R0_P8") (pintype "bidirectional"))
      (node (ref "D10") (pin "3") (pinfunction "RED_CATHODE_3") (pintype "bidirectional"))
    )
    (net (code "285") (name "Net-(CHIP_6-R1)") (class "Default")
      (node (ref "CHIP_6") (pin "P14") (pinfunction "R1_P14") (pintype "bidirectional"))
      (node (ref "D11") (pin "3") (pinfunction "RED_CATHODE_3") (pintype "bidirectional"))
    )
    (net (code "286") (name "Net-(CHIP_6-R2)") (class "Default")
      (node (ref "CHIP_6") (pin "P17") (pinfunction "R2_P17") (pintype "bidirectional"))
      (node (ref "D7") (pin "3") (pinfunction "RED_CATHODE_3") (pintype "bidirectional"))
    )
    (net (code "287") (name "Net-(CHIP_6-R3)") (class "Default")
      (node (ref "CHIP_6") (pin "P23") (pinfunction "R3_P23") (pintype "bidirectional"))
      (node (ref "D15") (pin "3") (pinfunction "RED_CATHODE_3") (pintype "bidirectional"))
    )
    (net (code "288") (name "Net-(CHIP_6-R4)") (class "Default")
      (node (ref "CHIP_6") (pin "P5") (pinfunction "R4_P5") (pintype "bidirectional"))
      (node (ref "D16") (pin "3") (pinfunction "RED_CATHODE_3") (pintype "bidirectional"))
    )
    (net (code "289") (name "Net-(CHIP_6-R5)") (class "Default")
      (node (ref "CHIP_6") (pin "P11") (pinfunction "R5_P11") (pintype "bidirectional"))
      (node (ref "D8") (pin "3") (pinfunction "RED_CATHODE_3") (pintype "bidirectional"))
    )
    (net (code "290") (name "Net-(CHIP_6-R6)") (class "Default")
      (node (ref "CHIP_6") (pin "P20") (pinfunction "R6_P20") (pintype "bidirectional"))
      (node (ref "D3") (pin "3") (pinfunction "RED_CATHODE_3") (pintype "bidirectional"))
    )
    (net (code "291") (name "Net-(CHIP_6-R7)") (class "Default")
      (node (ref "CHIP_6") (pin "P26") (pinfunction "R7_P26") (pintype "bidirectional"))
      (node (ref "D12") (pin "3") (pinfunction "RED_CATHODE_3") (pintype "bidirectional"))
    )
    (net (code "292") (name "Net-(CHIP_6-R8)") (class "Default")
      (node (ref "CHIP_6") (pin "P52") (pinfunction "R8_P52") (pintype "bidirectional"))
      (node (ref "D5") (pin "3") (pinfunction "RED_CATHODE_3") (pintype "bidirectional"))
    )
    (net (code "293") (name "Net-(CHIP_6-R9)") (class "Default")
      (node (ref "CHIP_6") (pin "P46") (pinfunction "R9_P46") (pintype "bidirectional"))
      (node (ref "D6") (pin "3") (pinfunction "RED_CATHODE_3") (pintype "bidirectional"))
    )
    (net (code "294") (name "Net-(CHIP_6-R10)") (class "Default")
      (node (ref "CHIP_6") (pin "P37") (pinfunction "R10_P37") (pintype "bidirectional"))
      (node (ref "D2") (pin "3") (pinfunction "RED_CATHODE_3") (pintype "bidirectional"))
    )
    (net (code "295") (name "Net-(CHIP_6-R11)") (class "Default")
      (node (ref "CHIP_6") (pin "P31") (pinfunction "R11_P31") (pintype "bidirectional"))
      (node (ref "D4") (pin "3") (pinfunction "RED_CATHODE_3") (pintype "bidirectional"))
    )
    (net (code "296") (name "Net-(CHIP_6-R12)") (class "Default")
      (node (ref "CHIP_6") (pin "P49") (pinfunction "R12_P49") (pintype "bidirectional"))
      (node (ref "D14") (pin "3") (pinfunction "RED_CATHODE_3") (pintype "bidirectional"))
    )
    (net (code "297") (name "Net-(CHIP_6-R13)") (class "Default")
      (node (ref "CHIP_6") (pin "P43") (pinfunction "R13_P43") (pintype "bidirectional"))
      (node (ref "D13") (pin "3") (pinfunction "RED_CATHODE_3") (pintype "bidirectional"))
    )
    (net (code "298") (name "Net-(CHIP_6-R14)") (class "Default")
      (node (ref "CHIP_6") (pin "P40") (pinfunction "R14_P40") (pintype "bidirectional"))
      (node (ref "D1") (pin "3") (pinfunction "RED_CATHODE_3") (pintype "bidirectional"))
    )
    (net (code "299") (name "Net-(CHIP_6-R15)") (class "Default")
      (node (ref "CHIP_6") (pin "P34") (pinfunction "R15_P34") (pintype "bidirectional"))
      (node (ref "D9") (pin "3") (pinfunction "RED_CATHODE_3") (pintype "bidirectional"))
    )
    (net (code "300") (name "VCC") (class "Default")
      (node (ref "C1") (pin "2") (pinfunction "2_2") (pintype "passive"))
      (node (ref "C2") (pin "2") (pinfunction "2_2") (pintype "passive"))
      (node (ref "C3") (pin "2") (pinfunction "2_2") (pintype "passive"))
      (node (ref "C4") (pin "2") (pinfunction "2_2") (pintype "passive"))
      (node (ref "C5") (pin "2") (pinfunction "2_2") (pintype "passive"))
      (node (ref "C6") (pin "2") (pinfunction "2_2") (pintype "passive"))
      (node (ref "CHIP_1") (pin "P54") (pinfunction "VCC_P54") (pintype "bidirectional"))
      (node (ref "CHIP_2") (pin "P54") (pinfunction "VCC_P54") (pintype "bidirectional"))
      (node (ref "CHIP_3") (pin "P54") (pinfunction "VCC_P54") (pintype "bidirectional"))
      (node (ref "CHIP_4") (pin "P54") (pinfunction "VCC_P54") (pintype "bidirectional"))
      (node (ref "CHIP_5") (pin "P54") (pinfunction "VCC_P54") (pintype "bidirectional"))
      (node (ref "CHIP_6") (pin "P54") (pinfunction "VCC_P54") (pintype "bidirectional"))
      (node (ref "D1") (pin "2") (pinfunction "CATHODE_2") (pintype "bidirectional"))
      (node (ref "D10") (pin "2") (pinfunction "CATHODE_2") (pintype "bidirectional"))
      (node (ref "D11") (pin "2") (pinfunction "CATHODE_2") (pintype "bidirectional"))
      (node (ref "D12") (pin "2") (pinfunction "CATHODE_2") (pintype "bidirectional"))
      (node (ref "D13") (pin "2") (pinfunction "CATHODE_2") (pintype "bidirectional"))
      (node (ref "D14") (pin "2") (pinfunction "CATHODE_2") (pintype "bidirectional"))
      (node (ref "D15") (pin "2") (pinfunction "CATHODE_2") (pintype "bidirectional"))
      (node (ref "D16") (pin "2") (pinfunction "CATHODE_2") (pintype "bidirectional"))
      (node (ref "D17") (pin "2") (pinfunction "CATHODE_2") (pintype "bidirectional"))
      (node (ref "D18") (pin "2") (pinfunction "CATHODE_2") (pintype "bidirectional"))
      (node (ref "D19") (pin "2") (pinfunction "CATHODE_2") (pintype "bidirectional"))
      (node (ref "D2") (pin "2") (pinfunction "CATHODE_2") (pintype "bidirectional"))
      (node (ref "D20") (pin "2") (pinfunction "CATHODE_2") (pintype "bidirectional"))
      (node (ref "D21") (pin "2") (pinfunction "CATHODE_2") (pintype "bidirectional"))
      (node (ref "D22") (pin "2") (pinfunction "CATHODE_2") (pintype "bidirectional"))
      (node (ref "D23") (pin "2") (pinfunction "CATHODE_2") (pintype "bidirectional"))
      (node (ref "D24") (pin "2") (pinfunction "CATHODE_2") (pintype "bidirectional"))
      (node (ref "D25") (pin "2") (pinfunction "CATHODE_2") (pintype "bidirectional"))
      (node (ref "D26") (pin "2") (pinfunction "CATHODE_2") (pintype "bidirectional"))
      (node (ref "D27") (pin "2") (pinfunction "CATHODE_2") (pintype "bidirectional"))
      (node (ref "D28") (pin "2") (pinfunction "CATHODE_2") (pintype "bidirectional"))
      (node (ref "D29") (pin "2") (pinfunction "CATHODE_2") (pintype "bidirectional"))
      (node (ref "D3") (pin "2") (pinfunction "CATHODE_2") (pintype "bidirectional"))
      (node (ref "D30") (pin "2") (pinfunction "CATHODE_2") (pintype "bidirectional"))
      (node (ref "D31") (pin "2") (pinfunction "CATHODE_2") (pintype "bidirectional"))
      (node (ref "D32") (pin "2") (pinfunction "CATHODE_2") (pintype "bidirectional"))
      (node (ref "D33") (pin "2") (pinfunction "CATHODE_2") (pintype "bidirectional"))
      (node (ref "D34") (pin "2") (pinfunction "CATHODE_2") (pintype "bidirectional"))
      (node (ref "D35") (pin "2") (pinfunction "CATHODE_2") (pintype "bidirectional"))
      (node (ref "D36") (pin "2") (pinfunction "CATHODE_2") (pintype "bidirectional"))
      (node (ref "D37") (pin "2") (pinfunction "CATHODE_2") (pintype "bidirectional"))
      (node (ref "D38") (pin "2") (pinfunction "CATHODE_2") (pintype "bidirectional"))
      (node (ref "D39") (pin "2") (pinfunction "CATHODE_2") (pintype "bidirectional"))
      (node (ref "D4") (pin "2") (pinfunction "CATHODE_2") (pintype "bidirectional"))
      (node (ref "D40") (pin "2") (pinfunction "CATHODE_2") (pintype "bidirectional"))
      (node (ref "D41") (pin "2") (pinfunction "CATHODE_2") (pintype "bidirectional"))
      (node (ref "D42") (pin "2") (pinfunction "CATHODE_2") (pintype "bidirectional"))
      (node (ref "D43") (pin "2") (pinfunction "CATHODE_2") (pintype "bidirectional"))
      (node (ref "D44") (pin "2") (pinfunction "CATHODE_2") (pintype "bidirectional"))
      (node (ref "D45") (pin "2") (pinfunction "CATHODE_2") (pintype "bidirectional"))
      (node (ref "D46") (pin "2") (pinfunction "CATHODE_2") (pintype "bidirectional"))
      (node (ref "D47") (pin "2") (pinfunction "CATHODE_2") (pintype "bidirectional"))
      (node (ref "D48") (pin "2") (pinfunction "CATHODE_2") (pintype "bidirectional"))
      (node (ref "D49") (pin "2") (pinfunction "CATHODE_2") (pintype "bidirectional"))
      (node (ref "D5") (pin "2") (pinfunction "CATHODE_2") (pintype "bidirectional"))
      (node (ref "D50") (pin "2") (pinfunction "CATHODE_2") (pintype "bidirectional"))
      (node (ref "D51") (pin "2") (pinfunction "CATHODE_2") (pintype "bidirectional"))
      (node (ref "D52") (pin "2") (pinfunction "CATHODE_2") (pintype "bidirectional"))
      (node (ref "D53") (pin "2") (pinfunction "CATHODE_2") (pintype "bidirectional"))
      (node (ref "D54") (pin "2") (pinfunction "CATHODE_2") (pintype "bidirectional"))
      (node (ref "D55") (pin "2") (pinfunction "CATHODE_2") (pintype "bidirectional"))
      (node (ref "D56") (pin "2") (pinfunction "CATHODE_2") (pintype "bidirectional"))
      (node (ref "D57") (pin "2") (pinfunction "CATHODE_2") (pintype "bidirectional"))
      (node (ref "D58") (pin "2") (pinfunction "CATHODE_2") (pintype "bidirectional"))
      (node (ref "D59") (pin "2") (pinfunction "CATHODE_2") (pintype "bidirectional"))
      (node (ref "D6") (pin "2") (pinfunction "CATHODE_2") (pintype "bidirectional"))
      (node (ref "D60") (pin "2") (pinfunction "CATHODE_2") (pintype "bidirectional"))
      (node (ref "D61") (pin "2") (pinfunction "CATHODE_2") (pintype "bidirectional"))
      (node (ref "D62") (pin "2") (pinfunction "CATHODE_2") (pintype "bidirectional"))
      (node (ref "D63") (pin "2") (pinfunction "CATHODE_2") (pintype "bidirectional"))
      (node (ref "D64") (pin "2") (pinfunction "CATHODE_2") (pintype "bidirectional"))
      (node (ref "D65") (pin "2") (pinfunction "CATHODE_2") (pintype "bidirectional"))
      (node (ref "D66") (pin "2") (pinfunction "CATHODE_2") (pintype "bidirectional"))
      (node (ref "D67") (pin "2") (pinfunction "CATHODE_2") (pintype "bidirectional"))
      (node (ref "D68") (pin "2") (pinfunction "CATHODE_2") (pintype "bidirectional"))
      (node (ref "D69") (pin "2") (pinfunction "CATHODE_2") (pintype "bidirectional"))
      (node (ref "D7") (pin "2") (pinfunction "CATHODE_2") (pintype "bidirectional"))
      (node (ref "D70") (pin "2") (pinfunction "CATHODE_2") (pintype "bidirectional"))
      (node (ref "D71") (pin "2") (pinfunction "CATHODE_2") (pintype "bidirectional"))
      (node (ref "D72") (pin "2") (pinfunction "CATHODE_2") (pintype "bidirectional"))
      (node (ref "D73") (pin "2") (pinfunction "CATHODE_2") (pintype "bidirectional"))
      (node (ref "D74") (pin "2") (pinfunction "CATHODE_2") (pintype "bidirectional"))
      (node (ref "D75") (pin "2") (pinfunction "CATHODE_2") (pintype "bidirectional"))
      (node (ref "D76") (pin "2") (pinfunction "CATHODE_2") (pintype "bidirectional"))
      (node (ref "D77") (pin "2") (pinfunction "CATHODE_2") (pintype "bidirectional"))
      (node (ref "D78") (pin "2") (pinfunction "CATHODE_2") (pintype "bidirectional"))
      (node (ref "D79") (pin "2") (pinfunction "CATHODE_2") (pintype "bidirectional"))
      (node (ref "D8") (pin "2") (pinfunction "CATHODE_2") (pintype "bidirectional"))
      (node (ref "D80") (pin "2") (pinfunction "CATHODE_2") (pintype "bidirectional"))
      (node (ref "D81") (pin "2") (pinfunction "CATHODE_2") (pintype "bidirectional"))
      (node (ref "D82") (pin "2") (pinfunction "CATHODE_2") (pintype "bidirectional"))
      (node (ref "D83") (pin "2") (pinfunction "CATHODE_2") (pintype "bidirectional"))
      (node (ref "D84") (pin "2") (pinfunction "CATHODE_2") (pintype "bidirectional"))
      (node (ref "D85") (pin "2") (pinfunction "CATHODE_2") (pintype "bidirectional"))
      (node (ref "D86") (pin "2") (pinfunction "CATHODE_2") (pintype "bidirectional"))
      (node (ref "D87") (pin "2") (pinfunction "CATHODE_2") (pintype "bidirectional"))
      (node (ref "D88") (pin "2") (pinfunction "CATHODE_2") (pintype "bidirectional"))
      (node (ref "D89") (pin "2") (pinfunction "CATHODE_2") (pintype "bidirectional"))
      (node (ref "D9") (pin "2") (pinfunction "CATHODE_2") (pintype "bidirectional"))
      (node (ref "D90") (pin "2") (pinfunction "CATHODE_2") (pintype "bidirectional"))
      (node (ref "D91") (pin "2") (pinfunction "CATHODE_2") (pintype "bidirectional"))
      (node (ref "D92") (pin "2") (pinfunction "CATHODE_2") (pintype "bidirectional"))
      (node (ref "D93") (pin "2") (pinfunction "CATHODE_2") (pintype "bidirectional"))
      (node (ref "D94") (pin "2") (pinfunction "CATHODE_2") (pintype "bidirectional"))
      (node (ref "D95") (pin "2") (pinfunction "CATHODE_2") (pintype "bidirectional"))
      (node (ref "D96") (pin "2") (pinfunction "CATHODE_2") (pintype "bidirectional"))
      (node (ref "U$1") (pin "P$2") (pinfunction "VCC_P$2") (pintype "bidirectional"))
    )
  )
)
